# Development_board.net
KiCad netlist of a schematic drawn in EAGLE
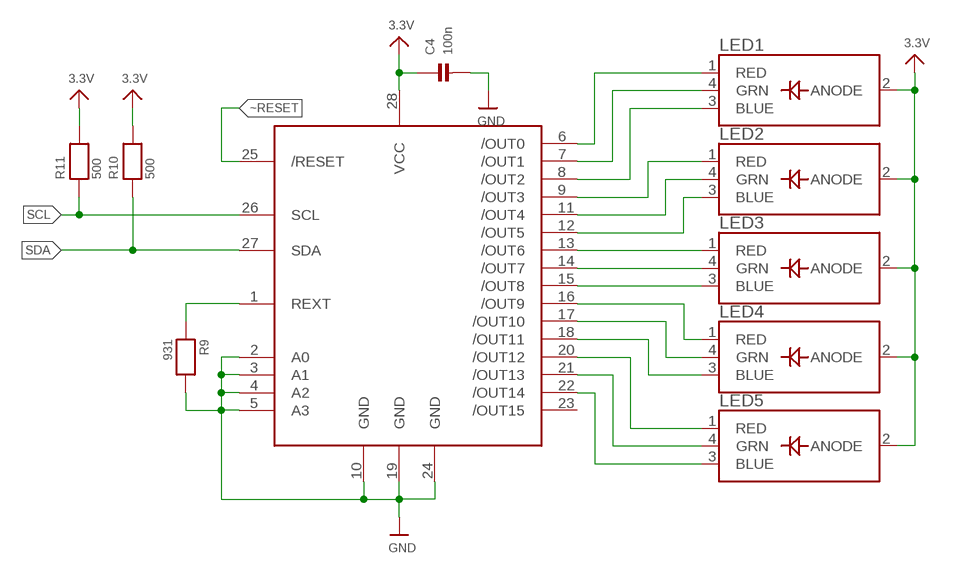
[diagram p0: schematic, sheet 1, part 1 of 3]
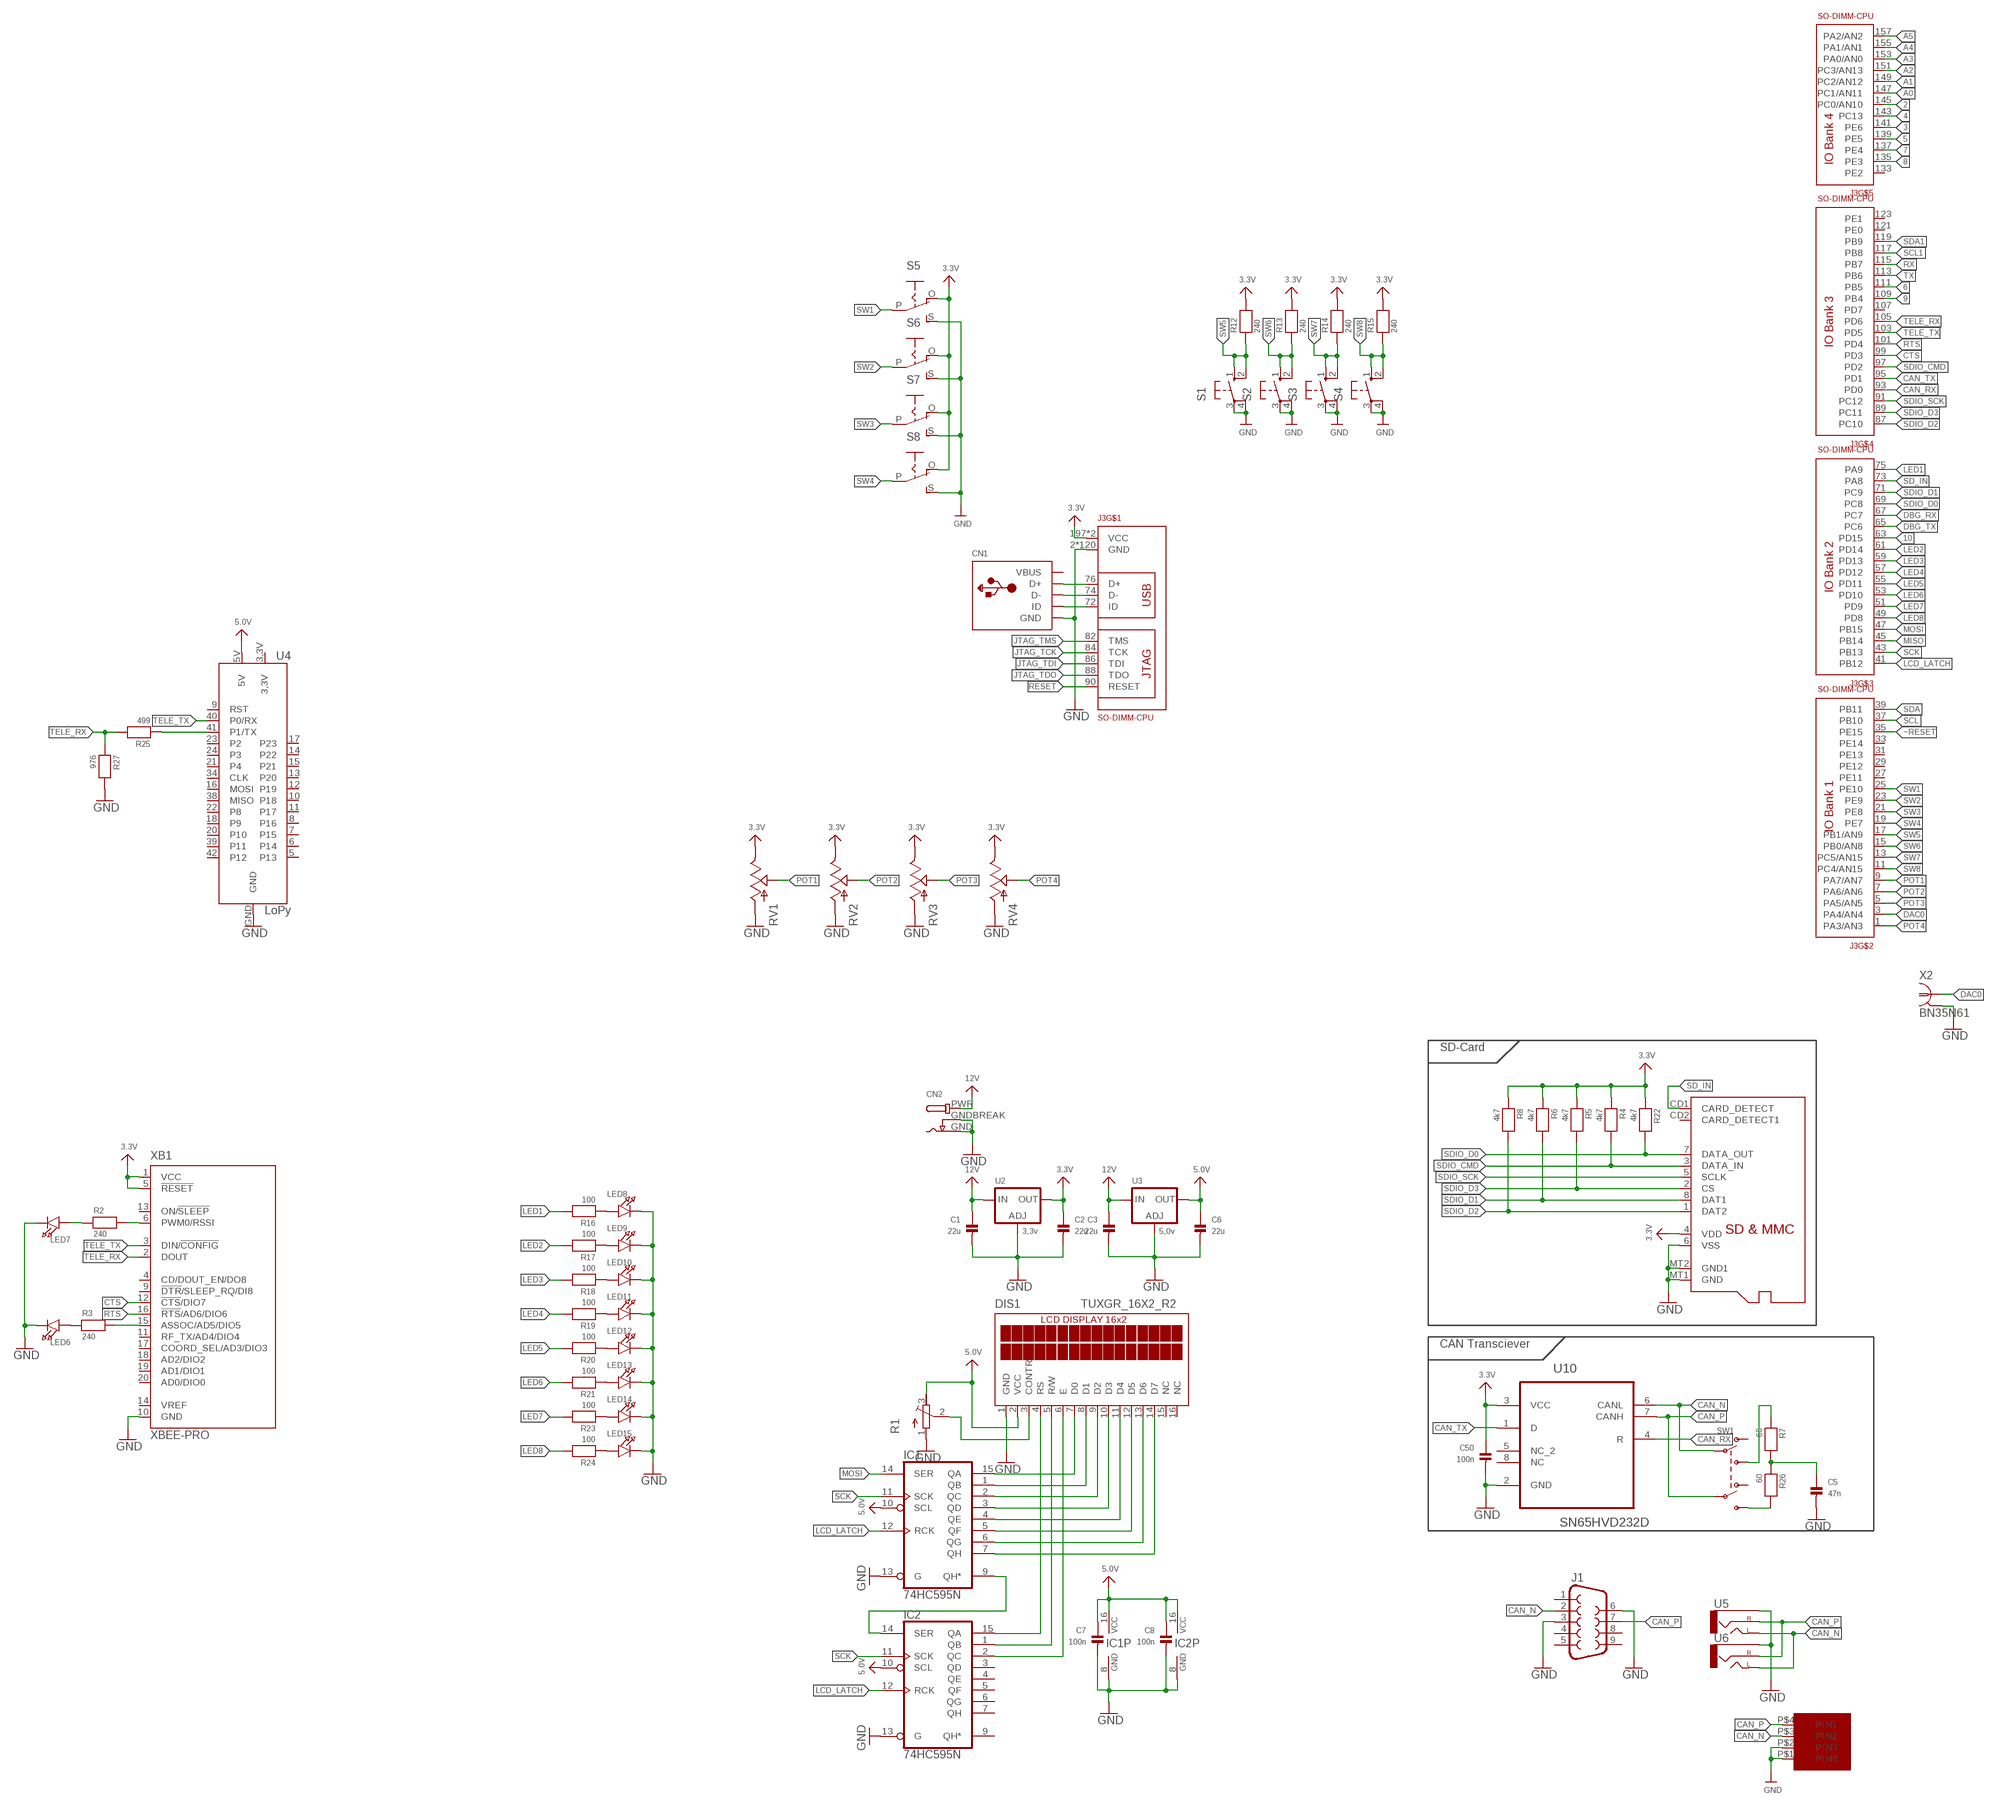
[diagram p1: schematic, sheet 1, part 2 of 3]
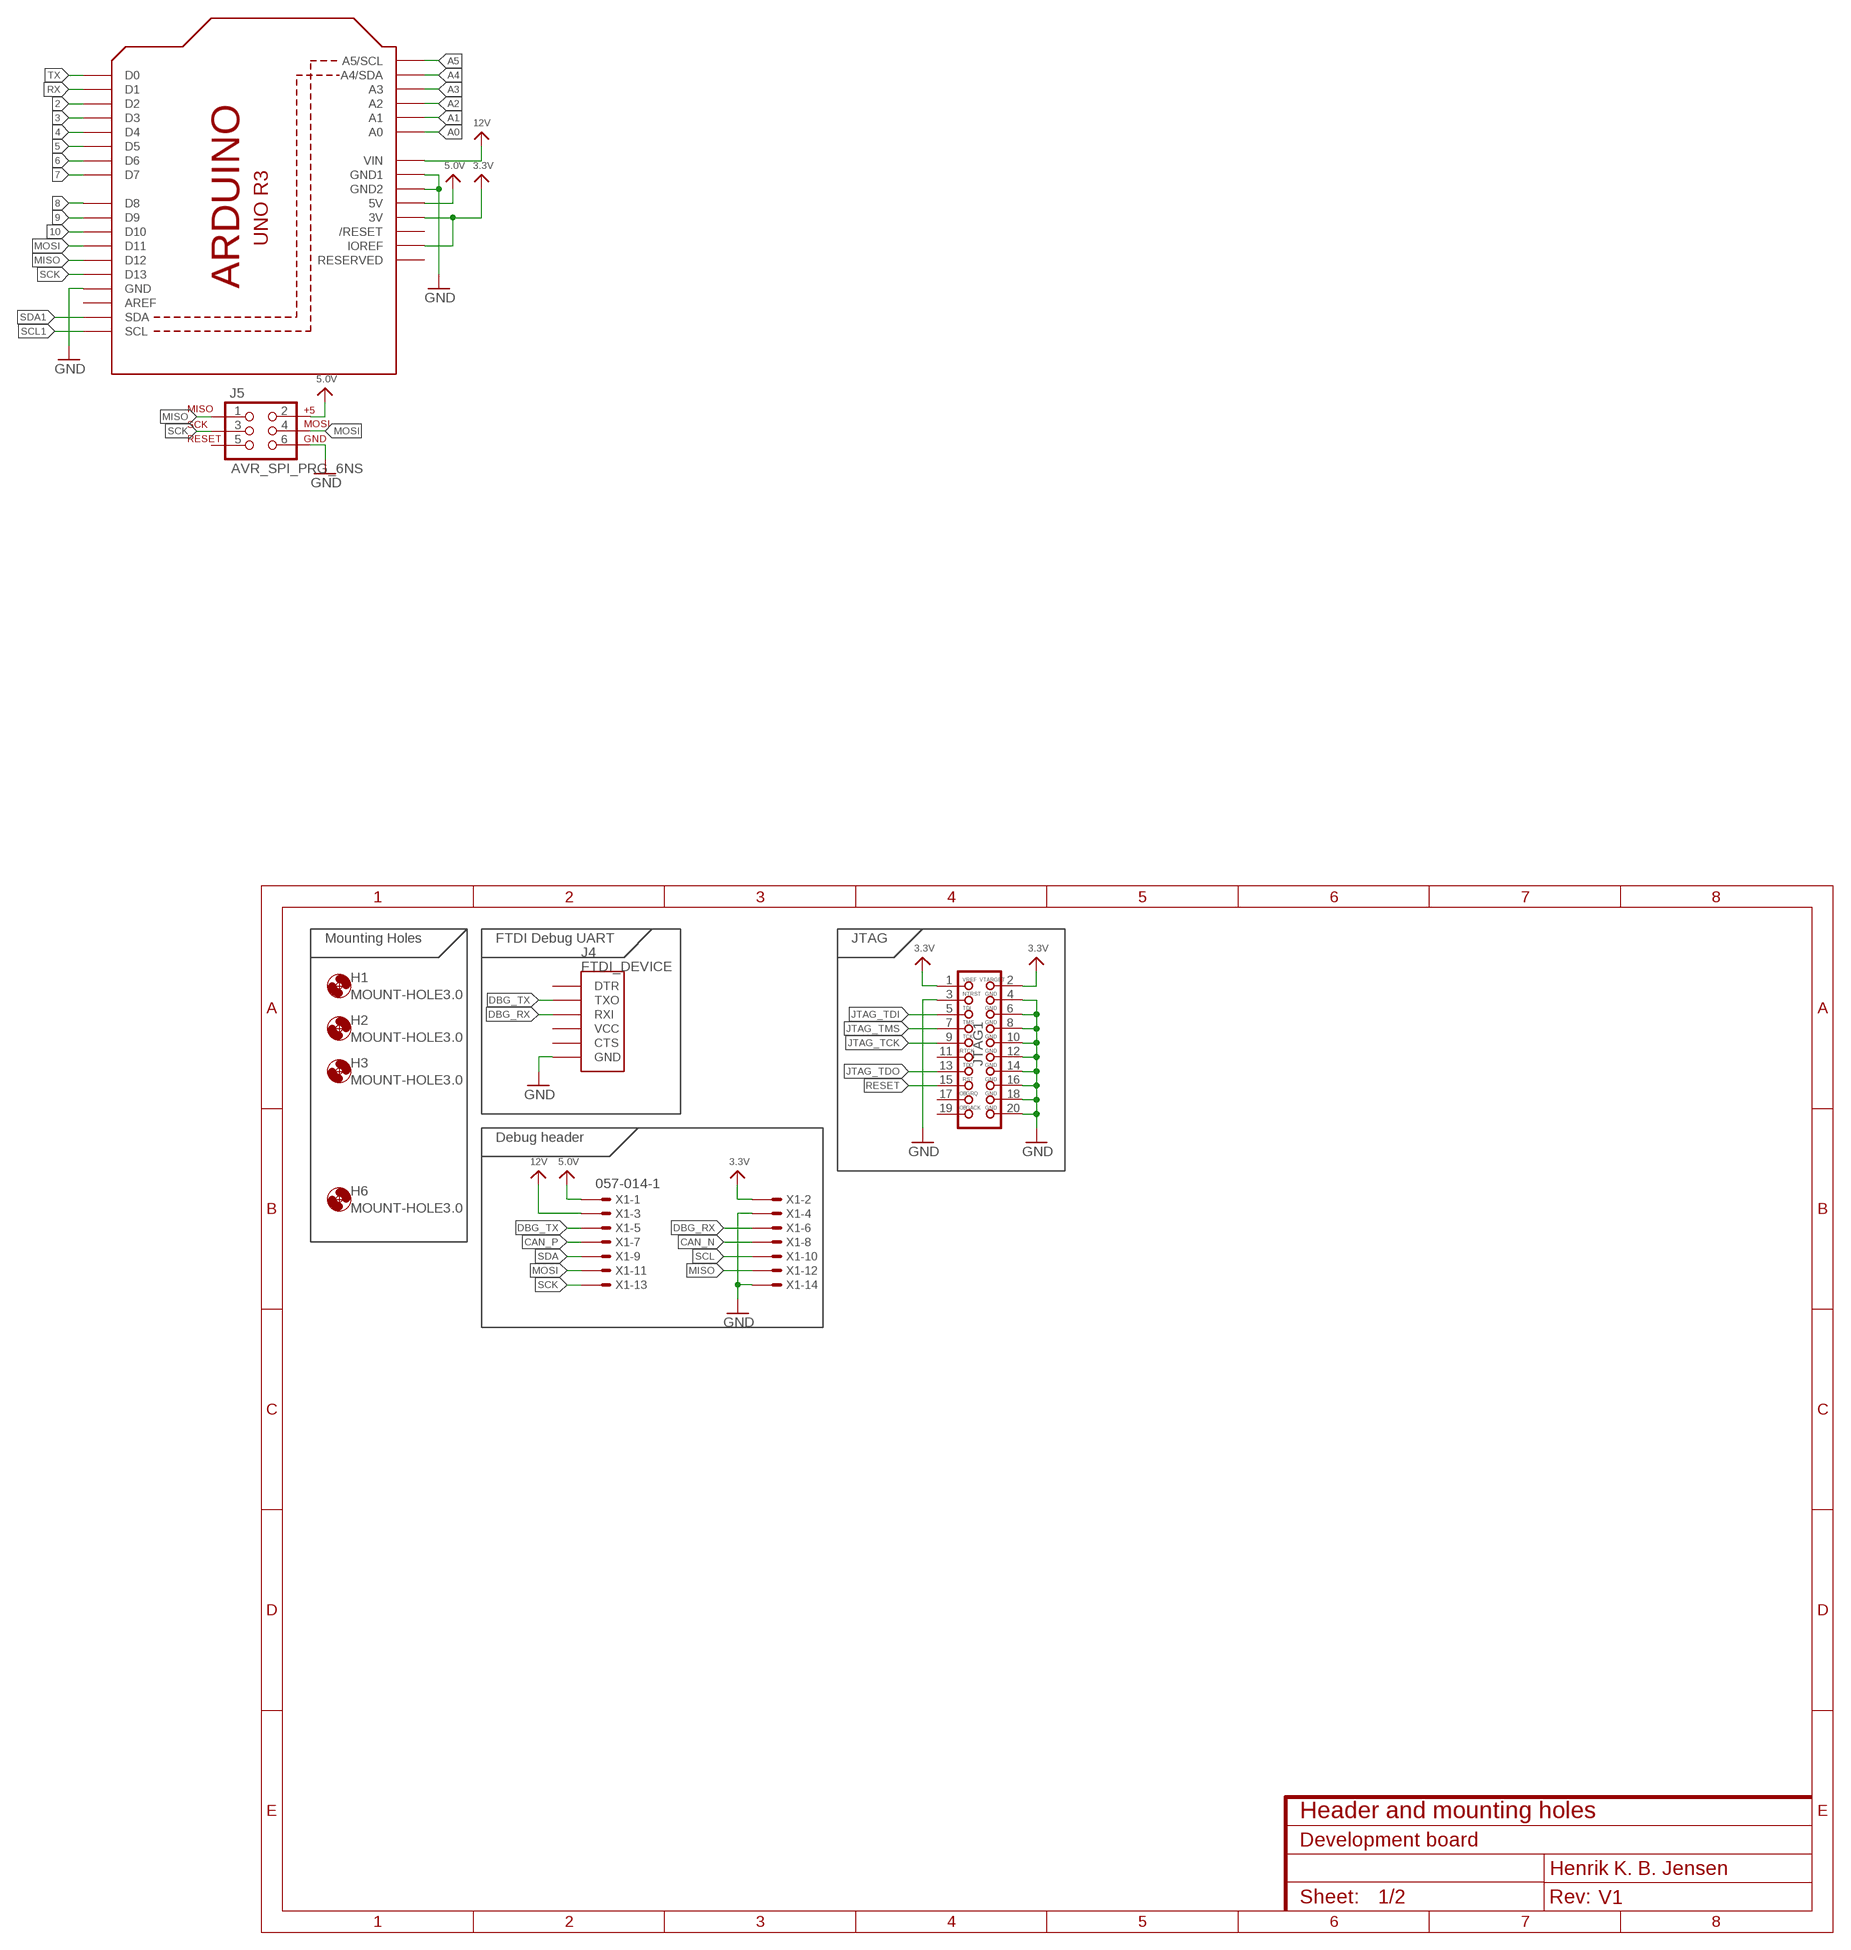
[diagram p2: schematic, sheet 1, part 3 of 3]
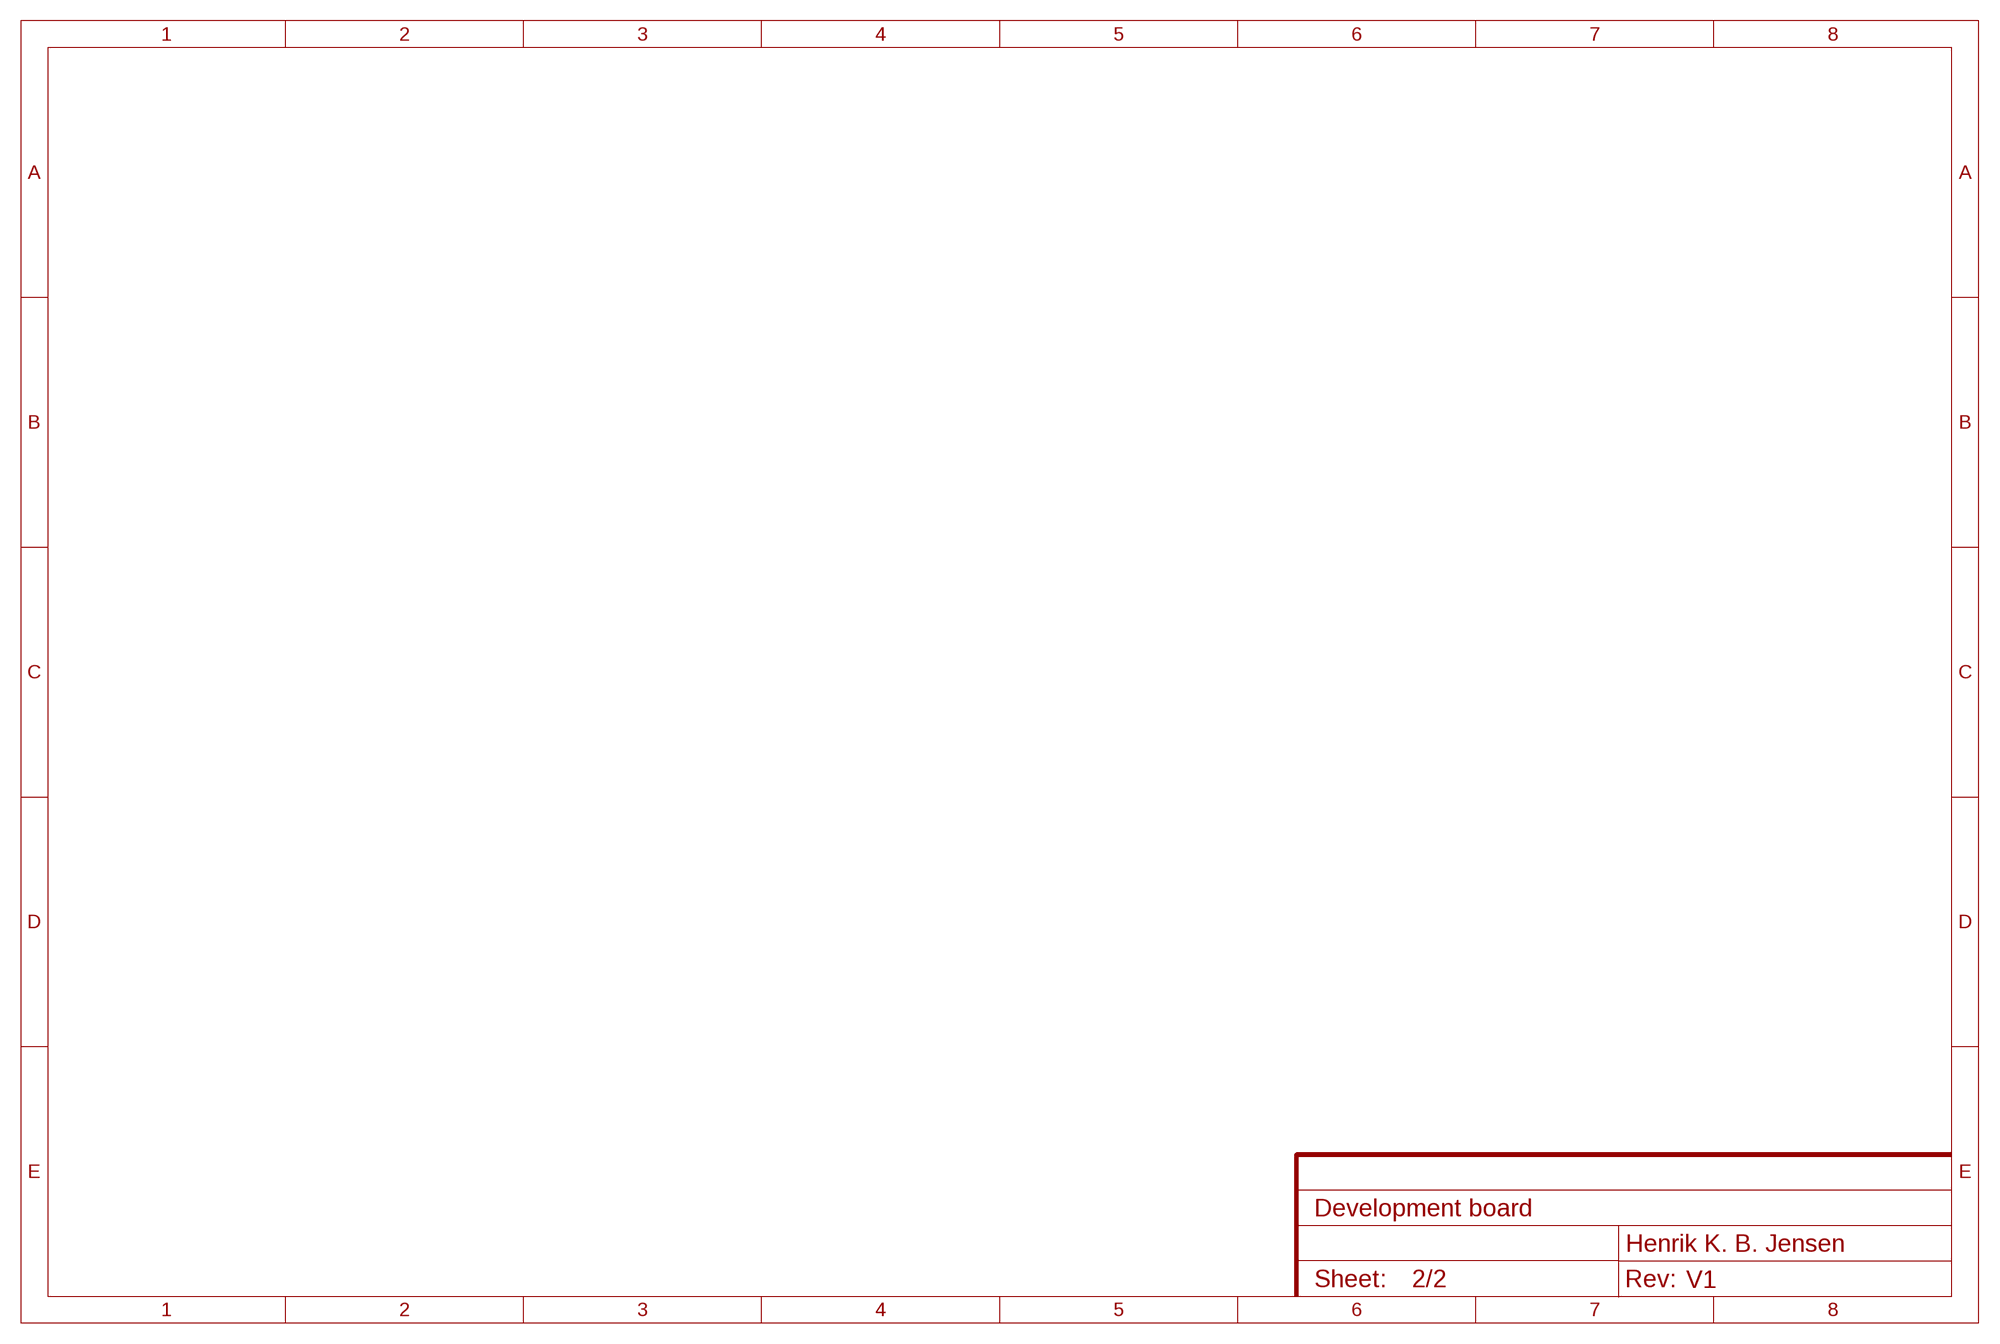
[diagram p3: schematic, sheet 2]

(export (version "E")
  (design (tool "Eeschema 10.0.6"))
  (components
    (comp (ref "C1")
      (value "22u")
      (footprint "eagle-import:_0805")
      (libsource (lib "eagle-import") (part "CAP_CERAMIC_0805"))
    )
    (comp (ref "C2")
      (value "22u")
      (footprint "eagle-import:_0805")
      (libsource (lib "eagle-import") (part "CAP_CERAMIC_0805"))
    )
    (comp (ref "C3")
      (value "22u")
      (footprint "eagle-import:_0805")
      (libsource (lib "eagle-import") (part "CAP_CERAMIC_0805"))
    )
    (comp (ref "C4")
      (value "100n")
      (footprint "eagle-import:_0603")
      (libsource (lib "eagle-import") (part "CAP_CERAMIC_0603"))
    )
    (comp (ref "C5")
      (value "47n")
      (footprint "eagle-import:_0603")
      (libsource (lib "eagle-import") (part "CAP_CERAMIC_0603"))
    )
    (comp (ref "C6")
      (value "22u")
      (footprint "eagle-import:_0805")
      (libsource (lib "eagle-import") (part "CAP_CERAMIC_0805"))
    )
    (comp (ref "C7")
      (value "100n")
      (footprint "eagle-import:_0603")
      (libsource (lib "eagle-import") (part "CAP_CERAMIC_0603"))
    )
    (comp (ref "C8")
      (value "100n")
      (footprint "eagle-import:_0603")
      (libsource (lib "eagle-import") (part "CAP_CERAMIC_0603"))
    )
    (comp (ref "C50")
      (value "100n")
      (footprint "eagle-import:_0603")
      (libsource (lib "eagle-import") (part "CAP_CERAMIC_0603"))
    )
    (comp (ref "CN1")
      (value "USBMINIBLARGE")
      (footprint "eagle-import:USB-MINIB_LARGER")
      (libsource (lib "eagle-import") (part "USBMINIBLARGE"))
    )
    (comp (ref "CN2")
      (value "DCBARRELPTH")
      (footprint "eagle-import:DCJACK_2MM_PTH")
      (libsource (lib "eagle-import") (part "DCBARRELPTH"))
    )
    (comp (ref "DIS1")
      (value "TUXGR_16X2_R2")
      (footprint "eagle-import:TUXGR_16X2_R2")
      (libsource (lib "eagle-import") (part "TUXGR_16X2_R2"))
    )
    (comp (ref "H1")
      (value "MOUNT-HOLE3.0")
      (footprint "eagle-import:3,0")
      (libsource (lib "eagle-import") (part "MOUNT-HOLE3.0"))
    )
    (comp (ref "H2")
      (value "MOUNT-HOLE3.0")
      (footprint "eagle-import:3,0")
      (libsource (lib "eagle-import") (part "MOUNT-HOLE3.0"))
    )
    (comp (ref "H3")
      (value "MOUNT-HOLE3.0")
      (footprint "eagle-import:3,0")
      (libsource (lib "eagle-import") (part "MOUNT-HOLE3.0"))
    )
    (comp (ref "H6")
      (value "MOUNT-HOLE3.0")
      (footprint "eagle-import:3,0")
      (libsource (lib "eagle-import") (part "MOUNT-HOLE3.0"))
    )
    (comp (ref "IC1")
      (value "74HC595N")
      (footprint "eagle-import:DIL16")
      (libsource (lib "eagle-import") (part "74595NHC"))
    )
    (comp (ref "IC2")
      (value "74HC595N")
      (footprint "eagle-import:DIL16")
      (libsource (lib "eagle-import") (part "74595NHC"))
    )
    (comp (ref "J1")
      (value "DB9FEMALE")
      (footprint "eagle-import:DB9")
      (libsource (lib "eagle-import") (part "DB9FEMALE"))
    )
    (comp (ref "J3")
      (value "SO-DIMM-CPU")
      (footprint "eagle-import:SODIMM-CONNECTOR-2.5V")
      (libsource (lib "eagle-import") (part "SO-DIMM-CPU"))
    )
    (comp (ref "J4")
      (value "FTDI_DEVICE")
      (footprint "eagle-import:FTDI_DEVICE_SIDE")
      (libsource (lib "eagle-import") (part "FTDI_DEVICE"))
    )
    (comp (ref "J5")
      (value "AVR_SPI_PRG_6NS")
      (footprint "eagle-import:2X3-NS")
      (libsource (lib "eagle-import") (part "AVR_SPI_PRG_6NS"))
    )
    (comp (ref "JTAG1")
      (value "JTAG-ARM")
      (footprint "eagle-import:JTAG-ARM")
      (libsource (lib "eagle-import") (part "JTAG-ARM"))
    )
    (comp (ref "LED1")
      (value "LED_RGB_PLCC4")
      (footprint "eagle-import:RGBLED_PLCC4")
      (libsource (lib "eagle-import") (part "LED_RGB_PLCC4"))
    )
    (comp (ref "LED2")
      (value "LED_RGB_PLCC4")
      (footprint "eagle-import:RGBLED_PLCC4")
      (libsource (lib "eagle-import") (part "LED_RGB_PLCC4"))
    )
    (comp (ref "LED3")
      (value "LED_RGB_PLCC4")
      (footprint "eagle-import:RGBLED_PLCC4")
      (libsource (lib "eagle-import") (part "LED_RGB_PLCC4"))
    )
    (comp (ref "LED4")
      (value "LED_RGB_PLCC4")
      (footprint "eagle-import:RGBLED_PLCC4")
      (libsource (lib "eagle-import") (part "LED_RGB_PLCC4"))
    )
    (comp (ref "LED5")
      (value "LED_RGB_PLCC4")
      (footprint "eagle-import:RGBLED_PLCC4")
      (libsource (lib "eagle-import") (part "LED_RGB_PLCC4"))
    )
    (comp (ref "LED6")
      (value "LED1206")
      (footprint "eagle-import:CHIPLED_1206")
      (libsource (lib "eagle-import") (part "LED1206"))
    )
    (comp (ref "LED7")
      (value "LED1206")
      (footprint "eagle-import:CHIPLED_1206")
      (libsource (lib "eagle-import") (part "LED1206"))
    )
    (comp (ref "LED8")
      (value "LED1206")
      (footprint "eagle-import:CHIPLED_1206")
      (libsource (lib "eagle-import") (part "LED1206"))
    )
    (comp (ref "LED9")
      (value "LED1206")
      (footprint "eagle-import:CHIPLED_1206")
      (libsource (lib "eagle-import") (part "LED1206"))
    )
    (comp (ref "LED10")
      (value "LED1206")
      (footprint "eagle-import:CHIPLED_1206")
      (libsource (lib "eagle-import") (part "LED1206"))
    )
    (comp (ref "LED11")
      (value "LED1206")
      (footprint "eagle-import:CHIPLED_1206")
      (libsource (lib "eagle-import") (part "LED1206"))
    )
    (comp (ref "LED12")
      (value "LED1206")
      (footprint "eagle-import:CHIPLED_1206")
      (libsource (lib "eagle-import") (part "LED1206"))
    )
    (comp (ref "LED13")
      (value "LED1206")
      (footprint "eagle-import:CHIPLED_1206")
      (libsource (lib "eagle-import") (part "LED1206"))
    )
    (comp (ref "LED14")
      (value "LED1206")
      (footprint "eagle-import:CHIPLED_1206")
      (libsource (lib "eagle-import") (part "LED1206"))
    )
    (comp (ref "LED15")
      (value "LED1206")
      (footprint "eagle-import:CHIPLED_1206")
      (libsource (lib "eagle-import") (part "LED1206"))
    )
    (comp (ref "R1")
      (value "R-TRIMM3296W")
      (footprint "eagle-import:RTRIM3296W")
      (libsource (lib "eagle-import") (part "R-TRIMM3296W"))
    )
    (comp (ref "R2")
      (value "240")
      (footprint "eagle-import:_0603")
      (libsource (lib "eagle-import") (part "RESISTOR_0603"))
    )
    (comp (ref "R3")
      (value "240")
      (footprint "eagle-import:_0603")
      (libsource (lib "eagle-import") (part "RESISTOR_0603"))
    )
    (comp (ref "R4")
      (value "4k7")
      (footprint "eagle-import:_0603")
      (libsource (lib "eagle-import") (part "RESISTOR_0603"))
    )
    (comp (ref "R5")
      (value "4k7")
      (footprint "eagle-import:_0603")
      (libsource (lib "eagle-import") (part "RESISTOR_0603"))
    )
    (comp (ref "R6")
      (value "4k7")
      (footprint "eagle-import:_0603")
      (libsource (lib "eagle-import") (part "RESISTOR_0603"))
    )
    (comp (ref "R7")
      (value "60")
      (footprint "eagle-import:_0603")
      (libsource (lib "eagle-import") (part "RESISTOR_0603"))
    )
    (comp (ref "R8")
      (value "4k7")
      (footprint "eagle-import:_0603")
      (libsource (lib "eagle-import") (part "RESISTOR_0603"))
    )
    (comp (ref "R9")
      (value "931")
      (footprint "eagle-import:_0603")
      (libsource (lib "eagle-import") (part "RESISTOR_0603"))
    )
    (comp (ref "R10")
      (value "500")
      (footprint "eagle-import:_0603")
      (libsource (lib "eagle-import") (part "RESISTOR_0603"))
    )
    (comp (ref "R11")
      (value "500")
      (footprint "eagle-import:_0603")
      (libsource (lib "eagle-import") (part "RESISTOR_0603"))
    )
    (comp (ref "R12")
      (value "240")
      (footprint "eagle-import:_0603")
      (libsource (lib "eagle-import") (part "RESISTOR_0603"))
    )
    (comp (ref "R13")
      (value "240")
      (footprint "eagle-import:_0603")
      (libsource (lib "eagle-import") (part "RESISTOR_0603"))
    )
    (comp (ref "R14")
      (value "240")
      (footprint "eagle-import:_0603")
      (libsource (lib "eagle-import") (part "RESISTOR_0603"))
    )
    (comp (ref "R15")
      (value "240")
      (footprint "eagle-import:_0603")
      (libsource (lib "eagle-import") (part "RESISTOR_0603"))
    )
    (comp (ref "R16")
      (value "100")
      (footprint "eagle-import:_0603")
      (libsource (lib "eagle-import") (part "RESISTOR_0603"))
    )
    (comp (ref "R17")
      (value "100")
      (footprint "eagle-import:_0603")
      (libsource (lib "eagle-import") (part "RESISTOR_0603"))
    )
    (comp (ref "R18")
      (value "100")
      (footprint "eagle-import:_0603")
      (libsource (lib "eagle-import") (part "RESISTOR_0603"))
    )
    (comp (ref "R19")
      (value "100")
      (footprint "eagle-import:_0603")
      (libsource (lib "eagle-import") (part "RESISTOR_0603"))
    )
    (comp (ref "R20")
      (value "100")
      (footprint "eagle-import:_0603")
      (libsource (lib "eagle-import") (part "RESISTOR_0603"))
    )
    (comp (ref "R21")
      (value "100")
      (footprint "eagle-import:_0603")
      (libsource (lib "eagle-import") (part "RESISTOR_0603"))
    )
    (comp (ref "R22")
      (value "4k7")
      (footprint "eagle-import:_0603")
      (libsource (lib "eagle-import") (part "RESISTOR_0603"))
    )
    (comp (ref "R23")
      (value "100")
      (footprint "eagle-import:_0603")
      (libsource (lib "eagle-import") (part "RESISTOR_0603"))
    )
    (comp (ref "R24")
      (value "100")
      (footprint "eagle-import:_0603")
      (libsource (lib "eagle-import") (part "RESISTOR_0603"))
    )
    (comp (ref "R25")
      (value "499")
      (footprint "eagle-import:_0603")
      (libsource (lib "eagle-import") (part "RESISTOR_0603"))
    )
    (comp (ref "R26")
      (value "60")
      (footprint "eagle-import:_0603")
      (libsource (lib "eagle-import") (part "RESISTOR_0603"))
    )
    (comp (ref "R27")
      (value "976")
      (footprint "eagle-import:_0603")
      (libsource (lib "eagle-import") (part "RESISTOR_0603"))
    )
    (comp (ref "RV1")
      (value "POT")
      (footprint "eagle-import:ALPS_POT")
      (libsource (lib "eagle-import") (part "POT"))
    )
    (comp (ref "RV2")
      (value "POT")
      (footprint "eagle-import:ALPS_POT")
      (libsource (lib "eagle-import") (part "POT"))
    )
    (comp (ref "RV3")
      (value "POT")
      (footprint "eagle-import:ALPS_POT")
      (libsource (lib "eagle-import") (part "POT"))
    )
    (comp (ref "RV4")
      (value "POT")
      (footprint "eagle-import:ALPS_POT")
      (libsource (lib "eagle-import") (part "POT"))
    )
    (comp (ref "S1")
      (value "10-XX")
      (footprint "eagle-import:B3F-10XX")
      (fields
        (field (name "MPN") "B3F-1000")
        (field (name "MPN_1") "B3F-1000")
        (field (name "OC_FARNELL") "176432")
        (field (name "OC_NEWARK") "36M3542")
      )
      (libsource (lib "eagle-import") (part "10-XX"))
    )
    (comp (ref "S2")
      (value "10-XX")
      (footprint "eagle-import:B3F-10XX")
      (fields
        (field (name "MPN") "B3F-1000")
        (field (name "MPN_1") "B3F-1000")
        (field (name "OC_FARNELL") "176432")
        (field (name "OC_NEWARK") "36M3542")
      )
      (libsource (lib "eagle-import") (part "10-XX"))
    )
    (comp (ref "S3")
      (value "10-XX")
      (footprint "eagle-import:B3F-10XX")
      (fields
        (field (name "MPN") "B3F-1000")
        (field (name "MPN_1") "B3F-1000")
        (field (name "OC_FARNELL") "176432")
        (field (name "OC_NEWARK") "36M3542")
      )
      (libsource (lib "eagle-import") (part "10-XX"))
    )
    (comp (ref "S4")
      (value "10-XX")
      (footprint "eagle-import:B3F-10XX")
      (fields
        (field (name "MPN") "B3F-1000")
        (field (name "MPN_1") "B3F-1000")
        (field (name "OC_FARNELL") "176432")
        (field (name "OC_NEWARK") "36M3542")
      )
      (libsource (lib "eagle-import") (part "10-XX"))
    )
    (comp (ref "S5")
      (value "EG1218S")
      (footprint "eagle-import:EG1218")
      (libsource (lib "eagle-import") (part "EG1218S"))
    )
    (comp (ref "S6")
      (value "EG1218S")
      (footprint "eagle-import:EG1218")
      (libsource (lib "eagle-import") (part "EG1218S"))
    )
    (comp (ref "S7")
      (value "EG1218S")
      (footprint "eagle-import:EG1218")
      (libsource (lib "eagle-import") (part "EG1218S"))
    )
    (comp (ref "S8")
      (value "EG1218S")
      (footprint "eagle-import:EG1218")
      (libsource (lib "eagle-import") (part "EG1218S"))
    )
    (comp (ref "SW1")
      (value "SWITCH_DPDT")
      (footprint "eagle-import:DPDT_SMT_JS202011SCQN")
      (libsource (lib "eagle-import") (part "SWITCH_DPDT"))
    )
    (comp (ref "U$2")
      (value "MICROSD")
      (footprint "eagle-import:MICROSD")
      (libsource (lib "eagle-import") (part "MICROSD"))
    )
    (comp (ref "U$21")
      (value "MICROFIT4")
      (footprint "eagle-import:43045-0400")
      (libsource (lib "eagle-import") (part "MICROFIT4"))
    )
    (comp (ref "U$30")
      (value "TLC59116")
      (footprint "eagle-import:TSSOP28")
      (libsource (lib "eagle-import") (part "TLC59116"))
    )
    (comp (ref "U1")
      (value "ARDUINOR3-DIMENSION")
      (footprint "eagle-import:ARDUINOR3")
      (libsource (lib "eagle-import") (part "ARDUINOR3-DIMENSION"))
    )
    (comp (ref "U2")
      (value "3,3v")
      (footprint "eagle-import:SOT223-R")
      (libsource (lib "eagle-import") (part "LM1117SOT223-REFLOW"))
    )
    (comp (ref "U3")
      (value "5,0v")
      (footprint "eagle-import:SOT223-R")
      (libsource (lib "eagle-import") (part "LM1117SOT223-REFLOW"))
    )
    (comp (ref "U4")
      (value "LoPy")
      (footprint "eagle-import:LOPY")
      (libsource (lib "eagle-import") (part "LOPY"))
    )
    (comp (ref "U5")
      (value "AUDIO-JACKPTH")
      (footprint "eagle-import:AUDIO-JACK")
      (libsource (lib "eagle-import") (part "AUDIO-JACKPTH"))
    )
    (comp (ref "U6")
      (value "AUDIO-JACKPTH")
      (footprint "eagle-import:AUDIO-JACK")
      (libsource (lib "eagle-import") (part "AUDIO-JACKPTH"))
    )
    (comp (ref "U10")
      (value "SN65HVD232D")
      (footprint "eagle-import:SOIC127P600X175-8N")
      (libsource (lib "eagle-import") (part "SN65HVD232D"))
    )
    (comp (ref "X1")
      (value "057-014-1")
      (footprint "eagle-import:057-014-1")
      (libsource (lib "eagle-import") (part "057-014-1"))
    )
    (comp (ref "X2")
      (value "BN35N61")
      (footprint "eagle-import:B35N61")
      (libsource (lib "eagle-import") (part "BN35N61"))
    )
    (comp (ref "XB1")
      (value "XBEE-PRO")
      (footprint "eagle-import:XBEE-PRO")
      (fields (field (name "MPN") "XBP24-AWI-001"))
      (libsource (lib "eagle-import") (part "XBEE-PRO"))
    )
  )
  (nets
    (net (code "1") (name "2") (class "Default")
      (node (ref "J3") (pin "145") (pinfunction "PC0/AN10_145") (pintype "bidirectional"))
      (node (ref "U1") (pin "D2") (pinfunction "D2_D2") (pintype "bidirectional"))
    )
    (net (code "2") (name "3") (class "Default")
      (node (ref "J3") (pin "141") (pinfunction "PE6_141") (pintype "bidirectional"))
      (node (ref "U1") (pin "D3") (pinfunction "D3_D3") (pintype "bidirectional"))
    )
    (net (code "3") (name "3.3V") (class "Default")
      (node (ref "C2") (pin "1") (pinfunction "P$1_1") (pintype "passive"))
      (node (ref "C4") (pin "1") (pinfunction "P$1_1") (pintype "passive"))
      (node (ref "C50") (pin "1") (pinfunction "P$1_1") (pintype "passive"))
      (node (ref "J3") (pin "197") (pinfunction "VCC_197") (pintype "bidirectional"))
      (node (ref "J3") (pin "199") (pinfunction "VCC_199") (pintype "bidirectional"))
      (node (ref "JTAG1") (pin "1") (pinfunction "1_1") (pintype "passive"))
      (node (ref "JTAG1") (pin "2") (pinfunction "2_2") (pintype "passive"))
      (node (ref "LED1") (pin "2") (pinfunction "ANODE_2") (pintype "power_in"))
      (node (ref "LED2") (pin "2") (pinfunction "ANODE_2") (pintype "power_in"))
      (node (ref "LED3") (pin "2") (pinfunction "ANODE_2") (pintype "power_in"))
      (node (ref "LED4") (pin "2") (pinfunction "ANODE_2") (pintype "power_in"))
      (node (ref "LED5") (pin "2") (pinfunction "ANODE_2") (pintype "power_in"))
      (node (ref "R10") (pin "2") (pinfunction "2_2") (pintype "passive"))
      (node (ref "R11") (pin "2") (pinfunction "2_2") (pintype "passive"))
      (node (ref "R12") (pin "2") (pinfunction "2_2") (pintype "passive"))
      (node (ref "R13") (pin "2") (pinfunction "2_2") (pintype "passive"))
      (node (ref "R14") (pin "2") (pinfunction "2_2") (pintype "passive"))
      (node (ref "R15") (pin "2") (pinfunction "2_2") (pintype "passive"))
      (node (ref "R22") (pin "1") (pinfunction "1_1") (pintype "passive"))
      (node (ref "R4") (pin "1") (pinfunction "1_1") (pintype "passive"))
      (node (ref "R5") (pin "1") (pinfunction "1_1") (pintype "passive"))
      (node (ref "R6") (pin "1") (pinfunction "1_1") (pintype "passive"))
      (node (ref "R8") (pin "1") (pinfunction "1_1") (pintype "passive"))
      (node (ref "RV1") (pin "P$1") (pinfunction "E_P$1") (pintype "passive"))
      (node (ref "RV2") (pin "P$1") (pinfunction "E_P$1") (pintype "passive"))
      (node (ref "RV3") (pin "P$1") (pinfunction "E_P$1") (pintype "passive"))
      (node (ref "RV4") (pin "P$1") (pinfunction "E_P$1") (pintype "passive"))
      (node (ref "S5") (pin "O") (pinfunction "O_O") (pintype "passive"))
      (node (ref "S6") (pin "O") (pinfunction "O_O") (pintype "passive"))
      (node (ref "S7") (pin "O") (pinfunction "O_O") (pintype "passive"))
      (node (ref "S8") (pin "O") (pinfunction "O_O") (pintype "passive"))
      (node (ref "U$2") (pin "4") (pinfunction "VDD_4") (pintype "power_in"))
      (node (ref "U$30") (pin "28") (pinfunction "VCC_28") (pintype "bidirectional"))
      (node (ref "U1") (pin "3V") (pinfunction "3V_3V") (pintype "power_in"))
      (node (ref "U1") (pin "IOREF") (pinfunction "IOREF_IOREF") (pintype "output"))
      (node (ref "U10") (pin "3") (pinfunction "VCC_3") (pintype "power_in"))
      (node (ref "U2") (pin "2") (pinfunction "OUT_2") (pintype "passive"))
      (node (ref "X1") (pin "2") (pinfunction "S_2") (pintype "passive"))
      (node (ref "XB1") (pin "1") (pinfunction "VCC_1") (pintype "power_in"))
      (node (ref "XB1") (pin "5") (pinfunction "~{RESET}_5") (pintype "input"))
    )
    (net (code "4") (name "4") (class "Default")
      (node (ref "J3") (pin "143") (pinfunction "PC13_143") (pintype "bidirectional"))
      (node (ref "U1") (pin "D4") (pinfunction "D4_D4") (pintype "bidirectional"))
    )
    (net (code "5") (name "5") (class "Default")
      (node (ref "J3") (pin "139") (pinfunction "PE5_139") (pintype "bidirectional"))
      (node (ref "U1") (pin "D5") (pinfunction "D5_D5") (pintype "bidirectional"))
    )
    (net (code "6") (name "5.0V") (class "Default")
      (node (ref "C6") (pin "1") (pinfunction "P$1_1") (pintype "passive"))
      (node (ref "C7") (pin "1") (pinfunction "P$1_1") (pintype "passive"))
      (node (ref "C8") (pin "1") (pinfunction "P$1_1") (pintype "passive"))
      (node (ref "DIS1") (pin "2") (pinfunction "VCC_2") (pintype "power_in"))
      (node (ref "IC1") (pin "10") (pinfunction "SCL_10") (pintype "input"))
      (node (ref "IC1") (pin "16") (pinfunction "VCC_16") (pintype "power_in"))
      (node (ref "IC2") (pin "10") (pinfunction "SCL_10") (pintype "input"))
      (node (ref "IC2") (pin "16") (pinfunction "VCC_16") (pintype "power_in"))
      (node (ref "J5") (pin "2") (pinfunction "2_2") (pintype "passive"))
      (node (ref "R1") (pin "3") (pinfunction "E_3") (pintype "passive"))
      (node (ref "U1") (pin "5V") (pinfunction "5V_5V") (pintype "power_in"))
      (node (ref "U3") (pin "2") (pinfunction "OUT_2") (pintype "passive"))
      (node (ref "U4") (pin "5V") (pinfunction "5V_5V") (pintype "bidirectional"))
      (node (ref "X1") (pin "1") (pinfunction "S_1") (pintype "passive"))
    )
    (net (code "7") (name "6") (class "Default")
      (node (ref "J3") (pin "111") (pinfunction "PB5_111") (pintype "bidirectional"))
      (node (ref "U1") (pin "D6") (pinfunction "D6_D6") (pintype "bidirectional"))
    )
    (net (code "8") (name "7") (class "Default")
      (node (ref "J3") (pin "137") (pinfunction "PE4_137") (pintype "bidirectional"))
      (node (ref "U1") (pin "D7") (pinfunction "D7_D7") (pintype "bidirectional"))
    )
    (net (code "9") (name "8") (class "Default")
      (node (ref "J3") (pin "135") (pinfunction "PE3_135") (pintype "bidirectional"))
      (node (ref "U1") (pin "D8") (pinfunction "D8_D8") (pintype "bidirectional"))
    )
    (net (code "10") (name "9") (class "Default")
      (node (ref "J3") (pin "109") (pinfunction "PB4_109") (pintype "bidirectional"))
      (node (ref "U1") (pin "D9") (pinfunction "D9_D9") (pintype "bidirectional"))
    )
    (net (code "11") (name "10") (class "Default")
      (node (ref "J3") (pin "63") (pinfunction "PD15_63") (pintype "bidirectional"))
      (node (ref "U1") (pin "D10") (pinfunction "D10_D10") (pintype "bidirectional"))
    )
    (net (code "12") (name "12V") (class "Default")
      (node (ref "C1") (pin "1") (pinfunction "P$1_1") (pintype "passive"))
      (node (ref "C3") (pin "1") (pinfunction "P$1_1") (pintype "passive"))
      (node (ref "CN2") (pin "PWR") (pinfunction "PWR_PWR") (pintype "power_in"))
      (node (ref "U1") (pin "VIN") (pinfunction "VIN_VIN") (pintype "power_in"))
      (node (ref "U2") (pin "3") (pinfunction "IN_3") (pintype "input"))
      (node (ref "U3") (pin "3") (pinfunction "IN_3") (pintype "input"))
      (node (ref "X1") (pin "3") (pinfunction "S_3") (pintype "passive"))
    )
    (net (code "13") (name "A0") (class "Default")
      (node (ref "J3") (pin "147") (pinfunction "PC1/AN11_147") (pintype "bidirectional"))
      (node (ref "U1") (pin "A0") (pinfunction "A0_A0") (pintype "bidirectional"))
    )
    (net (code "14") (name "A1") (class "Default")
      (node (ref "J3") (pin "149") (pinfunction "PC2/AN12_149") (pintype "bidirectional"))
      (node (ref "U1") (pin "A1") (pinfunction "A1_A1") (pintype "bidirectional"))
    )
    (net (code "15") (name "A2") (class "Default")
      (node (ref "J3") (pin "151") (pinfunction "PC3/AN13_151") (pintype "bidirectional"))
      (node (ref "U1") (pin "A2") (pinfunction "A2_A2") (pintype "bidirectional"))
    )
    (net (code "16") (name "A3") (class "Default")
      (node (ref "J3") (pin "153") (pinfunction "PA0/AN0_153") (pintype "bidirectional"))
      (node (ref "U1") (pin "A3") (pinfunction "A3_A3") (pintype "bidirectional"))
    )
    (net (code "17") (name "A4") (class "Default")
      (node (ref "J3") (pin "155") (pinfunction "PA1/AN1_155") (pintype "bidirectional"))
      (node (ref "U1") (pin "A4") (pinfunction "A4/SDA_A4") (pintype "bidirectional"))
    )
    (net (code "18") (name "A5") (class "Default")
      (node (ref "J3") (pin "157") (pinfunction "PA2/AN2_157") (pintype "bidirectional"))
      (node (ref "U1") (pin "A5") (pinfunction "A5/SCL_A5") (pintype "bidirectional"))
    )
    (net (code "19") (name "CAN_N") (class "Default")
      (node (ref "J1") (pin "2") (pinfunction "2_2") (pintype "passive"))
      (node (ref "SW1") (pin "P$2") (pinfunction "P1_P$2") (pintype "passive"))
      (node (ref "U$21") (pin "P$3") (pinfunction "PIN2_P$3") (pintype "bidirectional"))
      (node (ref "U10") (pin "6") (pinfunction "CANL_6") (pintype "output"))
      (node (ref "U5") (pin "TIP") (pinfunction "LEFT_TIP") (pintype "bidirectional"))
      (node (ref "U6") (pin "TIP") (pinfunction "LEFT_TIP") (pintype "bidirectional"))
      (node (ref "X1") (pin "8") (pinfunction "S_8") (pintype "passive"))
    )
    (net (code "20") (name "CAN_P") (class "Default")
      (node (ref "J1") (pin "7") (pinfunction "7_7") (pintype "passive"))
      (node (ref "SW1") (pin "P$5") (pinfunction "P2_P$5") (pintype "passive"))
      (node (ref "U$21") (pin "P$4") (pinfunction "PIN1_P$4") (pintype "bidirectional"))
      (node (ref "U10") (pin "7") (pinfunction "CANH_7") (pintype "output"))
      (node (ref "U5") (pin "RING") (pinfunction "RIGHT_RING") (pintype "bidirectional"))
      (node (ref "U6") (pin "RING") (pinfunction "RIGHT_RING") (pintype "bidirectional"))
      (node (ref "X1") (pin "7") (pinfunction "S_7") (pintype "passive"))
    )
    (net (code "21") (name "CAN_RX") (class "Default")
      (node (ref "J3") (pin "93") (pinfunction "PD0_93") (pintype "bidirectional"))
      (node (ref "U10") (pin "4") (pinfunction "R_4") (pintype "output"))
    )
    (net (code "22") (name "CAN_TX") (class "Default")
      (node (ref "J3") (pin "95") (pinfunction "PD1_95") (pintype "bidirectional"))
      (node (ref "U10") (pin "1") (pinfunction "D_1") (pintype "input"))
    )
    (net (code "23") (name "CTS") (class "Default")
      (node (ref "J3") (pin "99") (pinfunction "PD3_99") (pintype "bidirectional"))
      (node (ref "XB1") (pin "12") (pinfunction "~{CTS}/DIO7_12") (pintype "bidirectional"))
    )
    (net (code "24") (name "DAC0") (class "Default")
      (node (ref "J3") (pin "3") (pinfunction "PA4/AN4_3") (pintype "bidirectional"))
      (node (ref "X2") (pin "1") (pinfunction "1_1") (pintype "passive"))
    )
    (net (code "25") (name "DBG_RX") (class "Default")
      (node (ref "J3") (pin "67") (pinfunction "PC7_67") (pintype "bidirectional"))
      (node (ref "J4") (pin "P$3") (pinfunction "RXI_P$3") (pintype "bidirectional"))
      (node (ref "X1") (pin "6") (pinfunction "S_6") (pintype "passive"))
    )
    (net (code "26") (name "DBG_TX") (class "Default")
      (node (ref "J3") (pin "65") (pinfunction "PC6_65") (pintype "bidirectional"))
      (node (ref "J4") (pin "P$2") (pinfunction "TXO_P$2") (pintype "bidirectional"))
      (node (ref "X1") (pin "5") (pinfunction "S_5") (pintype "passive"))
    )
    (net (code "27") (name "GND") (class "Default")
      (node (ref "C1") (pin "2") (pinfunction "P$2_2") (pintype "passive"))
      (node (ref "C2") (pin "2") (pinfunction "P$2_2") (pintype "passive"))
      (node (ref "C3") (pin "2") (pinfunction "P$2_2") (pintype "passive"))
      (node (ref "C4") (pin "2") (pinfunction "P$2_2") (pintype "passive"))
      (node (ref "C5") (pin "2") (pinfunction "P$2_2") (pintype "passive"))
      (node (ref "C50") (pin "2") (pinfunction "P$2_2") (pintype "passive"))
      (node (ref "C6") (pin "2") (pinfunction "P$2_2") (pintype "passive"))
      (node (ref "C7") (pin "2") (pinfunction "P$2_2") (pintype "passive"))
      (node (ref "C8") (pin "2") (pinfunction "P$2_2") (pintype "passive"))
      (node (ref "CN1") (pin "GND") (pinfunction "GND_GND") (pintype "power_in"))
      (node (ref "CN2") (pin "GND") (pinfunction "GND_GND") (pintype "power_in"))
      (node (ref "CN2") (pin "GNDBREAK") (pinfunction "GNDBREAK_GNDBREAK") (pintype "power_in"))
      (node (ref "DIS1") (pin "1") (pinfunction "GND_1") (pintype "power_in"))
      (node (ref "IC1") (pin "13") (pinfunction "G_13") (pintype "input"))
      (node (ref "IC1") (pin "8") (pinfunction "GND_8") (pintype "power_in"))
      (node (ref "IC2") (pin "13") (pinfunction "G_13") (pintype "input"))
      (node (ref "IC2") (pin "8") (pinfunction "GND_8") (pintype "power_in"))
      (node (ref "J1") (pin "3") (pinfunction "3_3") (pintype "passive"))
      (node (ref "J1") (pin "6") (pinfunction "6_6") (pintype "passive"))
      (node (ref "J3") (pin "10") (pinfunction "GND_10") (pintype "bidirectional"))
      (node (ref "J3") (pin "100") (pinfunction "GND_100") (pintype "bidirectional"))
      (node (ref "J3") (pin "102") (pinfunction "GND_102") (pintype "bidirectional"))
      (node (ref "J3") (pin "104") (pinfunction "GND_104") (pintype "bidirectional"))
      (node (ref "J3") (pin "106") (pinfunction "GND_106") (pintype "bidirectional"))
      (node (ref "J3") (pin "108") (pinfunction "GND_108") (pintype "bidirectional"))
      (node (ref "J3") (pin "110") (pinfunction "GND_110") (pintype "bidirectional"))
      (node (ref "J3") (pin "112") (pinfunction "GND_112") (pintype "bidirectional"))
      (node (ref "J3") (pin "114") (pinfunction "GND_114") (pintype "bidirectional"))
      (node (ref "J3") (pin "116") (pinfunction "GND_116") (pintype "bidirectional"))
      (node (ref "J3") (pin "118") (pinfunction "GND_118") (pintype "bidirectional"))
      (node (ref "J3") (pin "12") (pinfunction "GND_12") (pintype "bidirectional"))
      (node (ref "J3") (pin "120") (pinfunction "GND_120") (pintype "bidirectional"))
      (node (ref "J3") (pin "122") (pinfunction "GND_122") (pintype "bidirectional"))
      (node (ref "J3") (pin "124") (pinfunction "GND_124") (pintype "bidirectional"))
      (node (ref "J3") (pin "125") (pinfunction "GND_125") (pintype "bidirectional"))
      (node (ref "J3") (pin "126") (pinfunction "GND_126") (pintype "bidirectional"))
      (node (ref "J3") (pin "127") (pinfunction "GND_127") (pintype "bidirectional"))
      (node (ref "J3") (pin "128") (pinfunction "GND_128") (pintype "bidirectional"))
      (node (ref "J3") (pin "129") (pinfunction "GND_129") (pintype "bidirectional"))
      (node (ref "J3") (pin "130") (pinfunction "GND_130") (pintype "bidirectional"))
      (node (ref "J3") (pin "131") (pinfunction "GND_131") (pintype "bidirectional"))
      (node (ref "J3") (pin "132") (pinfunction "GND_132") (pintype "bidirectional"))
      (node (ref "J3") (pin "134") (pinfunction "GND_134") (pintype "bidirectional"))
      (node (ref "J3") (pin "136") (pinfunction "GND_136") (pintype "bidirectional"))
      (node (ref "J3") (pin "138") (pinfunction "GND_138") (pintype "bidirectional"))
      (node (ref "J3") (pin "14") (pinfunction "GND_14") (pintype "bidirectional"))
      (node (ref "J3") (pin "140") (pinfunction "GND_140") (pintype "bidirectional"))
      (node (ref "J3") (pin "142") (pinfunction "GND_142") (pintype "bidirectional"))
      (node (ref "J3") (pin "144") (pinfunction "GND_144") (pintype "bidirectional"))
      (node (ref "J3") (pin "146") (pinfunction "GND_146") (pintype "bidirectional"))
      (node (ref "J3") (pin "148") (pinfunction "GND_148") (pintype "bidirectional"))
      (node (ref "J3") (pin "150") (pinfunction "GND_150") (pintype "bidirectional"))
      (node (ref "J3") (pin "152") (pinfunction "GND_152") (pintype "bidirectional"))
      (node (ref "J3") (pin "154") (pinfunction "GND_154") (pintype "bidirectional"))
      (node (ref "J3") (pin "156") (pinfunction "GND_156") (pintype "bidirectional"))
      (node (ref "J3") (pin "158") (pinfunction "GND_158") (pintype "bidirectional"))
      (node (ref "J3") (pin "159") (pinfunction "GND_159") (pintype "bidirectional"))
      (node (ref "J3") (pin "16") (pinfunction "GND_16") (pintype "bidirectional"))
      (node (ref "J3") (pin "160") (pinfunction "GND_160") (pintype "bidirectional"))
      (node (ref "J3") (pin "161") (pinfunction "GND_161") (pintype "bidirectional"))
      (node (ref "J3") (pin "162") (pinfunction "GND_162") (pintype "bidirectional"))
      (node (ref "J3") (pin "163") (pinfunction "GND_163") (pintype "bidirectional"))
      (node (ref "J3") (pin "164") (pinfunction "GND_164") (pintype "bidirectional"))
      (node (ref "J3") (pin "165") (pinfunction "GND_165") (pintype "bidirectional"))
      (node (ref "J3") (pin "166") (pinfunction "GND_166") (pintype "bidirectional"))
      (node (ref "J3") (pin "167") (pinfunction "GND_167") (pintype "bidirectional"))
      (node (ref "J3") (pin "168") (pinfunction "GND_168") (pintype "bidirectional"))
      (node (ref "J3") (pin "169") (pinfunction "GND_169") (pintype "bidirectional"))
      (node (ref "J3") (pin "170") (pinfunction "GND_170") (pintype "bidirectional"))
      (node (ref "J3") (pin "171") (pinfunction "GND_171") (pintype "bidirectional"))
      (node (ref "J3") (pin "172") (pinfunction "GND_172") (pintype "bidirectional"))
      (node (ref "J3") (pin "173") (pinfunction "GND_173") (pintype "bidirectional"))
      (node (ref "J3") (pin "174") (pinfunction "GND_174") (pintype "bidirectional"))
      (node (ref "J3") (pin "175") (pinfunction "GND_175") (pintype "bidirectional"))
      (node (ref "J3") (pin "176") (pinfunction "GND_176") (pintype "bidirectional"))
      (node (ref "J3") (pin "177") (pinfunction "GND_177") (pintype "bidirectional"))
      (node (ref "J3") (pin "178") (pinfunction "GND_178") (pintype "bidirectional"))
      (node (ref "J3") (pin "179") (pinfunction "GND_179") (pintype "bidirectional"))
      (node (ref "J3") (pin "18") (pinfunction "GND_18") (pintype "bidirectional"))
      (node (ref "J3") (pin "180") (pinfunction "GND_180") (pintype "bidirectional"))
      (node (ref "J3") (pin "181") (pinfunction "GND_181") (pintype "bidirectional"))
      (node (ref "J3") (pin "182") (pinfunction "GND_182") (pintype "bidirectional"))
      (node (ref "J3") (pin "183") (pinfunction "GND_183") (pintype "bidirectional"))
      (node (ref "J3") (pin "184") (pinfunction "GND_184") (pintype "bidirectional"))
      (node (ref "J3") (pin "185") (pinfunction "GND_185") (pintype "bidirectional"))
      (node (ref "J3") (pin "186") (pinfunction "GND_186") (pintype "bidirectional"))
      (node (ref "J3") (pin "187") (pinfunction "GND_187") (pintype "bidirectional"))
      (node (ref "J3") (pin "188") (pinfunction "GND_188") (pintype "bidirectional"))
      (node (ref "J3") (pin "189") (pinfunction "GND_189") (pintype "bidirectional"))
      (node (ref "J3") (pin "190") (pinfunction "GND_190") (pintype "bidirectional"))
      (node (ref "J3") (pin "191") (pinfunction "GND_191") (pintype "bidirectional"))
      (node (ref "J3") (pin "192") (pinfunction "GND_192") (pintype "bidirectional"))
      (node (ref "J3") (pin "193") (pinfunction "GND_193") (pintype "bidirectional"))
      (node (ref "J3") (pin "194") (pinfunction "GND_194") (pintype "bidirectional"))
      (node (ref "J3") (pin "195") (pinfunction "GND_195") (pintype "bidirectional"))
      (node (ref "J3") (pin "196") (pinfunction "GND_196") (pintype "bidirectional"))
      (node (ref "J3") (pin "198") (pinfunction "GND_198") (pintype "bidirectional"))
      (node (ref "J3") (pin "2") (pinfunction "GND_2") (pintype "bidirectional"))
      (node (ref "J3") (pin "20") (pinfunction "GND_20") (pintype "bidirectional"))
      (node (ref "J3") (pin "200") (pinfunction "GND_200") (pintype "bidirectional"))
      (node (ref "J3") (pin "22") (pinfunction "GND_22") (pintype "bidirectional"))
      (node (ref "J3") (pin "24") (pinfunction "GND_24") (pintype "bidirectional"))
      (node (ref "J3") (pin "26") (pinfunction "GND_26") (pintype "bidirectional"))
      (node (ref "J3") (pin "28") (pinfunction "GND_28") (pintype "bidirectional"))
      (node (ref "J3") (pin "30") (pinfunction "GND_30") (pintype "bidirectional"))
      (node (ref "J3") (pin "32") (pinfunction "GND_32") (pintype "bidirectional"))
      (node (ref "J3") (pin "34") (pinfunction "GND_34") (pintype "bidirectional"))
      (node (ref "J3") (pin "36") (pinfunction "GND_36") (pintype "bidirectional"))
      (node (ref "J3") (pin "38") (pinfunction "GND_38") (pintype "bidirectional"))
      (node (ref "J3") (pin "4") (pinfunction "GND_4") (pintype "bidirectional"))
      (node (ref "J3") (pin "40") (pinfunction "GND_40") (pintype "bidirectional"))
      (node (ref "J3") (pin "42") (pinfunction "GND_42") (pintype "bidirectional"))
      (node (ref "J3") (pin "44") (pinfunction "GND_44") (pintype "bidirectional"))
      (node (ref "J3") (pin "46") (pinfunction "GND_46") (pintype "bidirectional"))
      (node (ref "J3") (pin "48") (pinfunction "GND_48") (pintype "bidirectional"))
      (node (ref "J3") (pin "50") (pinfunction "GND_50") (pintype "bidirectional"))
      (node (ref "J3") (pin "52") (pinfunction "GND_52") (pintype "bidirectional"))
      (node (ref "J3") (pin "54") (pinfunction "GND_54") (pintype "bidirectional"))
      (node (ref "J3") (pin "56") (pinfunction "GND_56") (pintype "bidirectional"))
      (node (ref "J3") (pin "58") (pinfunction "GND_58") (pintype "bidirectional"))
      (node (ref "J3") (pin "6") (pinfunction "GND_6") (pintype "bidirectional"))
      (node (ref "J3") (pin "60") (pinfunction "GND_60") (pintype "bidirectional"))
      (node (ref "J3") (pin "62") (pinfunction "GND_62") (pintype "bidirectional"))
      (node (ref "J3") (pin "64") (pinfunction "GND_64") (pintype "bidirectional"))
      (node (ref "J3") (pin "66") (pinfunction "GND_66") (pintype "bidirectional"))
      (node (ref "J3") (pin "68") (pinfunction "GND_68") (pintype "bidirectional"))
      (node (ref "J3") (pin "70") (pinfunction "GND_70") (pintype "bidirectional"))
      (node (ref "J3") (pin "77") (pinfunction "GND_77") (pintype "bidirectional"))
      (node (ref "J3") (pin "78") (pinfunction "GND_78") (pintype "bidirectional"))
      (node (ref "J3") (pin "79") (pinfunction "GND_79") (pintype "bidirectional"))
      (node (ref "J3") (pin "8") (pinfunction "GND_8") (pintype "bidirectional"))
      (node (ref "J3") (pin "80") (pinfunction "GND_80") (pintype "bidirectional"))
      (node (ref "J3") (pin "81") (pinfunction "GND_81") (pintype "bidirectional"))
      (node (ref "J3") (pin "83") (pinfunction "GND_83") (pintype "bidirectional"))
      (node (ref "J3") (pin "85") (pinfunction "GND_85") (pintype "bidirectional"))
      (node (ref "J3") (pin "92") (pinfunction "GND_92") (pintype "bidirectional"))
      (node (ref "J3") (pin "94") (pinfunction "GND_94") (pintype "bidirectional"))
      (node (ref "J3") (pin "96") (pinfunction "GND_96") (pintype "bidirectional"))
      (node (ref "J3") (pin "98") (pinfunction "GND_98") (pintype "bidirectional"))
      (node (ref "J4") (pin "P$6") (pinfunction "GND_P$6") (pintype "bidirectional"))
      (node (ref "J5") (pin "6") (pinfunction "6_6") (pintype "passive"))
      (node (ref "JTAG1") (pin "10") (pinfunction "10_10") (pintype "passive"))
      (node (ref "JTAG1") (pin "12") (pinfunction "12_12") (pintype "passive"))
      (node (ref "JTAG1") (pin "14") (pinfunction "14_14") (pintype "passive"))
      (node (ref "JTAG1") (pin "16") (pinfunction "16_16") (pintype "passive"))
      (node (ref "JTAG1") (pin "18") (pinfunction "18_18") (pintype "passive"))
      (node (ref "JTAG1") (pin "20") (pinfunction "20_20") (pintype "passive"))
      (node (ref "JTAG1") (pin "3") (pinfunction "3_3") (pintype "passive"))
      (node (ref "JTAG1") (pin "4") (pinfunction "4_4") (pintype "passive"))
      (node (ref "JTAG1") (pin "6") (pinfunction "6_6") (pintype "passive"))
      (node (ref "JTAG1") (pin "8") (pinfunction "8_8") (pintype "passive"))
      (node (ref "LED10") (pin "C") (pinfunction "C_C") (pintype "passive"))
      (node (ref "LED11") (pin "C") (pinfunction "C_C") (pintype "passive"))
      (node (ref "LED12") (pin "C") (pinfunction "C_C") (pintype "passive"))
      (node (ref "LED13") (pin "C") (pinfunction "C_C") (pintype "passive"))
      (node (ref "LED14") (pin "C") (pinfunction "C_C") (pintype "passive"))
      (node (ref "LED15") (pin "C") (pinfunction "C_C") (pintype "passive"))
      (node (ref "LED6") (pin "C") (pinfunction "C_C") (pintype "passive"))
      (node (ref "LED7") (pin "C") (pinfunction "C_C") (pintype "passive"))
      (node (ref "LED8") (pin "C") (pinfunction "C_C") (pintype "passive"))
      (node (ref "LED9") (pin "C") (pinfunction "C_C") (pintype "passive"))
      (node (ref "R1") (pin "1") (pinfunction "A_1") (pintype "passive"))
      (node (ref "R27") (pin "2") (pinfunction "2_2") (pintype "passive"))
      (node (ref "R9") (pin "2") (pinfunction "2_2") (pintype "passive"))
      (node (ref "RV1") (pin "P$3") (pinfunction "A_P$3") (pintype "passive"))
      (node (ref "RV2") (pin "P$3") (pinfunction "A_P$3") (pintype "passive"))
      (node (ref "RV3") (pin "P$3") (pinfunction "A_P$3") (pintype "passive"))
      (node (ref "RV4") (pin "P$3") (pinfunction "A_P$3") (pintype "passive"))
      (node (ref "S1") (pin "3") (pinfunction "P_3") (pintype "passive"))
      (node (ref "S1") (pin "4") (pinfunction "P1_4") (pintype "passive"))
      (node (ref "S2") (pin "3") (pinfunction "P_3") (pintype "passive"))
      (node (ref "S2") (pin "4") (pinfunction "P1_4") (pintype "passive"))
      (node (ref "S3") (pin "3") (pinfunction "P_3") (pintype "passive"))
      (node (ref "S3") (pin "4") (pinfunction "P1_4") (pintype "passive"))
      (node (ref "S4") (pin "3") (pinfunction "P_3") (pintype "passive"))
      (node (ref "S4") (pin "4") (pinfunction "P1_4") (pintype "passive"))
      (node (ref "S5") (pin "S") (pinfunction "S_S") (pintype "passive"))
      (node (ref "S6") (pin "S") (pinfunction "S_S") (pintype "passive"))
      (node (ref "S7") (pin "S") (pinfunction "S_S") (pintype "passive"))
      (node (ref "S8") (pin "S") (pinfunction "S_S") (pintype "passive"))
      (node (ref "U$2") (pin "6") (pinfunction "VSS_6") (pintype "power_in"))
      (node (ref "U$2") (pin "MT1") (pinfunction "GND_MT1") (pintype "power_in"))
      (node (ref "U$2") (pin "MT2") (pinfunction "GND1_MT2") (pintype "power_in"))
      (node (ref "U$21") (pin "P$1") (pinfunction "PIN4_P$1") (pintype "bidirectional"))
      (node (ref "U$21") (pin "P$2") (pinfunction "PIN3_P$2") (pintype "bidirectional"))
      (node (ref "U$30") (pin "10") (pinfunction "GND_10") (pintype "bidirectional"))
      (node (ref "U$30") (pin "19") (pinfunction "GND_19") (pintype "bidirectional"))
      (node (ref "U$30") (pin "2") (pinfunction "A0_2") (pintype "bidirectional"))
      (node (ref "U$30") (pin "24") (pinfunction "GND_24") (pintype "bidirectional"))
      (node (ref "U$30") (pin "3") (pinfunction "A1_3") (pintype "bidirectional"))
      (node (ref "U$30") (pin "4") (pinfunction "A2_4") (pintype "bidirectional"))
      (node (ref "U$30") (pin "5") (pinfunction "A3_5") (pintype "bidirectional"))
      (node (ref "U1") (pin "GND") (pinfunction "GND_GND") (pintype "power_in"))
      (node (ref "U1") (pin "GND1") (pinfunction "GND1_GND1") (pintype "power_in"))
      (node (ref "U1") (pin "GND2") (pinfunction "GND2_GND2") (pintype "power_in"))
      (node (ref "U10") (pin "2") (pinfunction "GND_2") (pintype "passive"))
      (node (ref "U2") (pin "1") (pinfunction "ADJ_1") (pintype "input"))
      (node (ref "U3") (pin "1") (pinfunction "ADJ_1") (pintype "input"))
      (node (ref "U4") (pin "GND") (pinfunction "GND_GND") (pintype "bidirectional"))
      (node (ref "U5") (pin "SLEEVE") (pinfunction "SLEEVE_SLEEVE") (pintype "bidirectional"))
      (node (ref "U6") (pin "SLEEVE") (pinfunction "SLEEVE_SLEEVE") (pintype "bidirectional"))
      (node (ref "X1") (pin "14") (pinfunction "S_14") (pintype "passive"))
      (node (ref "X1") (pin "4") (pinfunction "S_4") (pintype "passive"))
      (node (ref "X2") (pin "2") (pinfunction "GND_2") (pintype "power_in"))
      (node (ref "XB1") (pin "10") (pinfunction "GND_10") (pintype "power_in"))
    )
    (net (code "28") (name "JTAG_TCK") (class "Default")
      (node (ref "J3") (pin "84") (pinfunction "TCK_84") (pintype "bidirectional"))
      (node (ref "JTAG1") (pin "9") (pinfunction "9_9") (pintype "passive"))
    )
    (net (code "29") (name "JTAG_TDI") (class "Default")
      (node (ref "J3") (pin "86") (pinfunction "TDI_86") (pintype "bidirectional"))
      (node (ref "JTAG1") (pin "5") (pinfunction "5_5") (pintype "passive"))
    )
    (net (code "30") (name "JTAG_TDO") (class "Default")
      (node (ref "J3") (pin "88") (pinfunction "TDO_88") (pintype "bidirectional"))
      (node (ref "JTAG1") (pin "13") (pinfunction "13_13") (pintype "passive"))
    )
    (net (code "31") (name "JTAG_TMS") (class "Default")
      (node (ref "J3") (pin "82") (pinfunction "TMS_82") (pintype "bidirectional"))
      (node (ref "JTAG1") (pin "7") (pinfunction "7_7") (pintype "passive"))
    )
    (net (code "32") (name "LCD_LATCH") (class "Default")
      (node (ref "IC1") (pin "12") (pinfunction "RCK_12") (pintype "input"))
      (node (ref "IC2") (pin "12") (pinfunction "RCK_12") (pintype "input"))
      (node (ref "J3") (pin "41") (pinfunction "PB12_41") (pintype "bidirectional"))
    )
    (net (code "33") (name "LED1") (class "Default")
      (node (ref "J3") (pin "75") (pinfunction "PA9_75") (pintype "bidirectional"))
      (node (ref "R16") (pin "2") (pinfunction "2_2") (pintype "passive"))
    )
    (net (code "34") (name "LED2") (class "Default")
      (node (ref "J3") (pin "61") (pinfunction "PD14_61") (pintype "bidirectional"))
      (node (ref "R17") (pin "2") (pinfunction "2_2") (pintype "passive"))
    )
    (net (code "35") (name "LED3") (class "Default")
      (node (ref "J3") (pin "59") (pinfunction "PD13_59") (pintype "bidirectional"))
      (node (ref "R18") (pin "2") (pinfunction "2_2") (pintype "passive"))
    )
    (net (code "36") (name "LED4") (class "Default")
      (node (ref "J3") (pin "57") (pinfunction "PD12_57") (pintype "bidirectional"))
      (node (ref "R19") (pin "2") (pinfunction "2_2") (pintype "passive"))
    )
    (net (code "37") (name "LED5") (class "Default")
      (node (ref "J3") (pin "55") (pinfunction "PD11_55") (pintype "bidirectional"))
      (node (ref "R20") (pin "2") (pinfunction "2_2") (pintype "passive"))
    )
    (net (code "38") (name "LED6") (class "Default")
      (node (ref "J3") (pin "53") (pinfunction "PD10_53") (pintype "bidirectional"))
      (node (ref "R21") (pin "2") (pinfunction "2_2") (pintype "passive"))
    )
    (net (code "39") (name "LED7") (class "Default")
      (node (ref "J3") (pin "51") (pinfunction "PD9_51") (pintype "bidirectional"))
      (node (ref "R23") (pin "2") (pinfunction "2_2") (pintype "passive"))
    )
    (net (code "40") (name "LED8") (class "Default")
      (node (ref "J3") (pin "49") (pinfunction "PD8_49") (pintype "bidirectional"))
      (node (ref "R24") (pin "2") (pinfunction "2_2") (pintype "passive"))
    )
    (net (code "41") (name "MISO") (class "Default")
      (node (ref "J3") (pin "45") (pinfunction "PB14_45") (pintype "bidirectional"))
      (node (ref "J5") (pin "1") (pinfunction "1_1") (pintype "passive"))
      (node (ref "U1") (pin "D12") (pinfunction "D12_D12") (pintype "bidirectional"))
      (node (ref "X1") (pin "12") (pinfunction "S_12") (pintype "passive"))
    )
    (net (code "42") (name "MOSI") (class "Default")
      (node (ref "IC1") (pin "14") (pinfunction "SER_14") (pintype "input"))
      (node (ref "J3") (pin "47") (pinfunction "PB15_47") (pintype "bidirectional"))
      (node (ref "J5") (pin "4") (pinfunction "4_4") (pintype "passive"))
      (node (ref "U1") (pin "D11") (pinfunction "D11_D11") (pintype "bidirectional"))
      (node (ref "X1") (pin "11") (pinfunction "S_11") (pintype "passive"))
    )
    (net (code "43") (name "Net-(C5-P$1)") (class "Default")
      (node (ref "C5") (pin "1") (pinfunction "P$1_1") (pintype "passive"))
      (node (ref "R26") (pin "1") (pinfunction "1_1") (pintype "passive"))
      (node (ref "R7") (pin "2") (pinfunction "2_2") (pintype "passive"))
    )
    (net (code "44") (name "Net-(DIS1-CONTR)") (class "Default")
      (node (ref "DIS1") (pin "3") (pinfunction "CONTR_3") (pintype "input"))
      (node (ref "R1") (pin "2") (pinfunction "S_2") (pintype "passive"))
    )
    (net (code "45") (name "Net-(DIS1-D0)") (class "Default")
      (node (ref "DIS1") (pin "7") (pinfunction "D0_7") (pintype "input"))
      (node (ref "IC1") (pin "15") (pinfunction "QA_15") (pintype "tri_state"))
    )
    (net (code "46") (name "Net-(DIS1-D1)") (class "Default")
      (node (ref "DIS1") (pin "8") (pinfunction "D1_8") (pintype "input"))
      (node (ref "IC1") (pin "1") (pinfunction "QB_1") (pintype "tri_state"))
    )
    (net (code "47") (name "Net-(DIS1-D2)") (class "Default")
      (node (ref "DIS1") (pin "9") (pinfunction "D2_9") (pintype "input"))
      (node (ref "IC1") (pin "2") (pinfunction "QC_2") (pintype "tri_state"))
    )
    (net (code "48") (name "Net-(DIS1-D3)") (class "Default")
      (node (ref "DIS1") (pin "10") (pinfunction "D3_10") (pintype "input"))
      (node (ref "IC1") (pin "3") (pinfunction "QD_3") (pintype "tri_state"))
    )
    (net (code "49") (name "Net-(DIS1-D4)") (class "Default")
      (node (ref "DIS1") (pin "11") (pinfunction "D4_11") (pintype "input"))
      (node (ref "IC1") (pin "4") (pinfunction "QE_4") (pintype "tri_state"))
    )
    (net (code "50") (name "Net-(DIS1-D5)") (class "Default")
      (node (ref "DIS1") (pin "12") (pinfunction "D5_12") (pintype "input"))
      (node (ref "IC1") (pin "5") (pinfunction "QF_5") (pintype "tri_state"))
    )
    (net (code "51") (name "Net-(DIS1-D6)") (class "Default")
      (node (ref "DIS1") (pin "13") (pinfunction "D6_13") (pintype "input"))
      (node (ref "IC1") (pin "6") (pinfunction "QG_6") (pintype "tri_state"))
    )
    (net (code "52") (name "Net-(DIS1-D7)") (class "Default")
      (node (ref "DIS1") (pin "14") (pinfunction "D7_14") (pintype "input"))
      (node (ref "IC1") (pin "7") (pinfunction "QH_7") (pintype "tri_state"))
    )
    (net (code "53") (name "Net-(DIS1-E)") (class "Default")
      (node (ref "DIS1") (pin "6") (pinfunction "E_6") (pintype "input"))
      (node (ref "IC2") (pin "2") (pinfunction "QC_2") (pintype "tri_state"))
    )
    (net (code "54") (name "Net-(DIS1-RS)") (class "Default")
      (node (ref "DIS1") (pin "4") (pinfunction "RS_4") (pintype "input"))
      (node (ref "IC2") (pin "15") (pinfunction "QA_15") (pintype "tri_state"))
    )
    (net (code "55") (name "Net-(DIS1-R{slash}W)") (class "Default")
      (node (ref "DIS1") (pin "5") (pinfunction "R/W_5") (pintype "input"))
      (node (ref "IC2") (pin "1") (pinfunction "QB_1") (pintype "tri_state"))
    )
    (net (code "56") (name "Net-(IC1A-QH*)") (class "Default")
      (node (ref "IC1") (pin "9") (pinfunction "QH*_9") (pintype "tri_state"))
      (node (ref "IC2") (pin "14") (pinfunction "SER_14") (pintype "input"))
    )
    (net (code "57") (name "Net-(J3A-D+)") (class "Default")
      (node (ref "CN1") (pin "D+") (pinfunction "D+_D+") (pintype "bidirectional"))
      (node (ref "J3") (pin "76") (pinfunction "D+_76") (pintype "bidirectional"))
    )
    (net (code "58") (name "Net-(J3A-D-)") (class "Default")
      (node (ref "CN1") (pin "D-") (pinfunction "D-_D-") (pintype "bidirectional"))
      (node (ref "J3") (pin "74") (pinfunction "D-_74") (pintype "bidirectional"))
    )
    (net (code "59") (name "Net-(J3A-ID)") (class "Default")
      (node (ref "CN1") (pin "ID") (pinfunction "ID_ID") (pintype "bidirectional"))
      (node (ref "J3") (pin "72") (pinfunction "ID_72") (pintype "bidirectional"))
    )
    (net (code "60") (name "Net-(LED1-BLUE)") (class "Default")
      (node (ref "LED1") (pin "3") (pinfunction "BLUE_3") (pintype "bidirectional"))
      (node (ref "U$30") (pin "8") (pinfunction "/OUT2_8") (pintype "bidirectional"))
    )
    (net (code "61") (name "Net-(LED1-GRN)") (class "Default")
      (node (ref "LED1") (pin "4") (pinfunction "GRN_4") (pintype "bidirectional"))
      (node (ref "U$30") (pin "7") (pinfunction "/OUT1_7") (pintype "bidirectional"))
    )
    (net (code "62") (name "Net-(LED1-RED)") (class "Default")
      (node (ref "LED1") (pin "1") (pinfunction "RED_1") (pintype "bidirectional"))
      (node (ref "U$30") (pin "6") (pinfunction "/OUT0_6") (pintype "bidirectional"))
    )
    (net (code "63") (name "Net-(LED2-BLUE)") (class "Default")
      (node (ref "LED2") (pin "3") (pinfunction "BLUE_3") (pintype "bidirectional"))
      (node (ref "U$30") (pin "12") (pinfunction "/OUT5_12") (pintype "bidirectional"))
    )
    (net (code "64") (name "Net-(LED2-GRN)") (class "Default")
      (node (ref "LED2") (pin "4") (pinfunction "GRN_4") (pintype "bidirectional"))
      (node (ref "U$30") (pin "11") (pinfunction "/OUT4_11") (pintype "bidirectional"))
    )
    (net (code "65") (name "Net-(LED2-RED)") (class "Default")
      (node (ref "LED2") (pin "1") (pinfunction "RED_1") (pintype "bidirectional"))
      (node (ref "U$30") (pin "9") (pinfunction "/OUT3_9") (pintype "bidirectional"))
    )
    (net (code "66") (name "Net-(LED3-BLUE)") (class "Default")
      (node (ref "LED3") (pin "3") (pinfunction "BLUE_3") (pintype "bidirectional"))
      (node (ref "U$30") (pin "15") (pinfunction "/OUT8_15") (pintype "bidirectional"))
    )
    (net (code "67") (name "Net-(LED3-GRN)") (class "Default")
      (node (ref "LED3") (pin "4") (pinfunction "GRN_4") (pintype "bidirectional"))
      (node (ref "U$30") (pin "14") (pinfunction "/OUT7_14") (pintype "bidirectional"))
    )
    (net (code "68") (name "Net-(LED3-RED)") (class "Default")
      (node (ref "LED3") (pin "1") (pinfunction "RED_1") (pintype "bidirectional"))
      (node (ref "U$30") (pin "13") (pinfunction "/OUT6_13") (pintype "bidirectional"))
    )
    (net (code "69") (name "Net-(LED4-BLUE)") (class "Default")
      (node (ref "LED4") (pin "3") (pinfunction "BLUE_3") (pintype "bidirectional"))
      (node (ref "U$30") (pin "18") (pinfunction "/OUT11_18") (pintype "bidirectional"))
    )
    (net (code "70") (name "Net-(LED4-GRN)") (class "Default")
      (node (ref "LED4") (pin "4") (pinfunction "GRN_4") (pintype "bidirectional"))
      (node (ref "U$30") (pin "17") (pinfunction "/OUT10_17") (pintype "bidirectional"))
    )
    (net (code "71") (name "Net-(LED4-RED)") (class "Default")
      (node (ref "LED4") (pin "1") (pinfunction "RED_1") (pintype "bidirectional"))
      (node (ref "U$30") (pin "16") (pinfunction "/OUT9_16") (pintype "bidirectional"))
    )
    (net (code "72") (name "Net-(LED5-BLUE)") (class "Default")
      (node (ref "LED5") (pin "3") (pinfunction "BLUE_3") (pintype "bidirectional"))
      (node (ref "U$30") (pin "22") (pinfunction "/OUT14_22") (pintype "bidirectional"))
    )
    (net (code "73") (name "Net-(LED5-GRN)") (class "Default")
      (node (ref "LED5") (pin "4") (pinfunction "GRN_4") (pintype "bidirectional"))
      (node (ref "U$30") (pin "21") (pinfunction "/OUT13_21") (pintype "bidirectional"))
    )
    (net (code "74") (name "Net-(LED5-RED)") (class "Default")
      (node (ref "LED5") (pin "1") (pinfunction "RED_1") (pintype "bidirectional"))
      (node (ref "U$30") (pin "20") (pinfunction "/OUT12_20") (pintype "bidirectional"))
    )
    (net (code "75") (name "Net-(LED6-PadA)") (class "Default")
      (node (ref "LED6") (pin "A") (pinfunction "A_A") (pintype "passive"))
      (node (ref "R3") (pin "1") (pinfunction "1_1") (pintype "passive"))
    )
    (net (code "76") (name "Net-(LED7-PadA)") (class "Default")
      (node (ref "LED7") (pin "A") (pinfunction "A_A") (pintype "passive"))
      (node (ref "R2") (pin "1") (pinfunction "1_1") (pintype "passive"))
    )
    (net (code "77") (name "Net-(LED8-PadA)") (class "Default")
      (node (ref "LED8") (pin "A") (pinfunction "A_A") (pintype "passive"))
      (node (ref "R16") (pin "1") (pinfunction "1_1") (pintype "passive"))
    )
    (net (code "78") (name "Net-(LED9-PadA)") (class "Default")
      (node (ref "LED9") (pin "A") (pinfunction "A_A") (pintype "passive"))
      (node (ref "R17") (pin "1") (pinfunction "1_1") (pintype "passive"))
    )
    (net (code "79") (name "Net-(LED10-PadA)") (class "Default")
      (node (ref "LED10") (pin "A") (pinfunction "A_A") (pintype "passive"))
      (node (ref "R18") (pin "1") (pinfunction "1_1") (pintype "passive"))
    )
    (net (code "80") (name "Net-(LED11-PadA)") (class "Default")
      (node (ref "LED11") (pin "A") (pinfunction "A_A") (pintype "passive"))
      (node (ref "R19") (pin "1") (pinfunction "1_1") (pintype "passive"))
    )
    (net (code "81") (name "Net-(LED12-PadA)") (class "Default")
      (node (ref "LED12") (pin "A") (pinfunction "A_A") (pintype "passive"))
      (node (ref "R20") (pin "1") (pinfunction "1_1") (pintype "passive"))
    )
    (net (code "82") (name "Net-(LED13-PadA)") (class "Default")
      (node (ref "LED13") (pin "A") (pinfunction "A_A") (pintype "passive"))
      (node (ref "R21") (pin "1") (pinfunction "1_1") (pintype "passive"))
    )
    (net (code "83") (name "Net-(LED14-PadA)") (class "Default")
      (node (ref "LED14") (pin "A") (pinfunction "A_A") (pintype "passive"))
      (node (ref "R23") (pin "1") (pinfunction "1_1") (pintype "passive"))
    )
    (net (code "84") (name "Net-(LED15-PadA)") (class "Default")
      (node (ref "LED15") (pin "A") (pinfunction "A_A") (pintype "passive"))
      (node (ref "R24") (pin "1") (pinfunction "1_1") (pintype "passive"))
    )
    (net (code "85") (name "Net-(SW1-S1)") (class "Default")
      (node (ref "R7") (pin "1") (pinfunction "1_1") (pintype "passive"))
      (node (ref "SW1") (pin "P$3") (pinfunction "S1_P$3") (pintype "passive"))
    )
    (net (code "86") (name "Net-(SW1-S2)") (class "Default")
      (node (ref "R26") (pin "2") (pinfunction "2_2") (pintype "passive"))
      (node (ref "SW1") (pin "P$4") (pinfunction "S2_P$4") (pintype "passive"))
    )
    (net (code "87") (name "Net-(U$30-REXT)") (class "Default")
      (node (ref "R9") (pin "1") (pinfunction "1_1") (pintype "passive"))
      (node (ref "U$30") (pin "1") (pinfunction "REXT_1") (pintype "bidirectional"))
    )
    (net (code "88") (name "Net-(U4-P1{slash}TX)") (class "Default")
      (node (ref "R25") (pin "1") (pinfunction "1_1") (pintype "passive"))
      (node (ref "U4") (pin "41") (pinfunction "P1/TX_41") (pintype "bidirectional"))
    )
    (net (code "89") (name "Net-(XB1-ASSOC{slash}AD5{slash}DIO5)") (class "Default")
      (node (ref "R3") (pin "2") (pinfunction "2_2") (pintype "passive"))
      (node (ref "XB1") (pin "15") (pinfunction "ASSOC/AD5/DIO5_15") (pintype "bidirectional"))
    )
    (net (code "90") (name "Net-(XB1-PWM0{slash}RSSI)") (class "Default")
      (node (ref "R2") (pin "2") (pinfunction "2_2") (pintype "passive"))
      (node (ref "XB1") (pin "6") (pinfunction "PWM0/RSSI_6") (pintype "output"))
    )
    (net (code "91") (name "POT1") (class "Default")
      (node (ref "J3") (pin "9") (pinfunction "PA7/AN7_9") (pintype "bidirectional"))
      (node (ref "RV1") (pin "P$2") (pinfunction "S_P$2") (pintype "passive"))
    )
    (net (code "92") (name "POT2") (class "Default")
      (node (ref "J3") (pin "7") (pinfunction "PA6/AN6_7") (pintype "bidirectional"))
      (node (ref "RV2") (pin "P$2") (pinfunction "S_P$2") (pintype "passive"))
    )
    (net (code "93") (name "POT3") (class "Default")
      (node (ref "J3") (pin "5") (pinfunction "PA5/AN5_5") (pintype "bidirectional"))
      (node (ref "RV3") (pin "P$2") (pinfunction "S_P$2") (pintype "passive"))
    )
    (net (code "94") (name "POT4") (class "Default")
      (node (ref "J3") (pin "1") (pinfunction "PA3/AN3_1") (pintype "bidirectional"))
      (node (ref "RV4") (pin "P$2") (pinfunction "S_P$2") (pintype "passive"))
    )
    (net (code "95") (name "RESET") (class "Default")
      (node (ref "J3") (pin "90") (pinfunction "RESET_90") (pintype "bidirectional"))
      (node (ref "JTAG1") (pin "15") (pinfunction "15_15") (pintype "passive"))
    )
    (net (code "96") (name "RTS") (class "Default")
      (node (ref "J3") (pin "101") (pinfunction "PD4_101") (pintype "bidirectional"))
      (node (ref "XB1") (pin "16") (pinfunction "~{RTS}/AD6/DIO6_16") (pintype "bidirectional"))
    )
    (net (code "97") (name "RX") (class "Default")
      (node (ref "J3") (pin "115") (pinfunction "PB7_115") (pintype "bidirectional"))
      (node (ref "U1") (pin "D1") (pinfunction "D1_D1") (pintype "bidirectional"))
    )
    (net (code "98") (name "SCK") (class "Default")
      (node (ref "IC1") (pin "11") (pinfunction "SCK_11") (pintype "input"))
      (node (ref "IC2") (pin "11") (pinfunction "SCK_11") (pintype "input"))
      (node (ref "J3") (pin "43") (pinfunction "PB13_43") (pintype "bidirectional"))
      (node (ref "J5") (pin "3") (pinfunction "3_3") (pintype "passive"))
      (node (ref "U1") (pin "D13") (pinfunction "D13_D13") (pintype "bidirectional"))
      (node (ref "X1") (pin "13") (pinfunction "S_13") (pintype "passive"))
    )
    (net (code "99") (name "SCL") (class "Default")
      (node (ref "J3") (pin "37") (pinfunction "PB10_37") (pintype "bidirectional"))
      (node (ref "R11") (pin "1") (pinfunction "1_1") (pintype "passive"))
      (node (ref "U$30") (pin "26") (pinfunction "SCL_26") (pintype "bidirectional"))
      (node (ref "X1") (pin "10") (pinfunction "S_10") (pintype "passive"))
    )
    (net (code "100") (name "SCL1") (class "Default")
      (node (ref "J3") (pin "117") (pinfunction "PB8_117") (pintype "bidirectional"))
      (node (ref "U1") (pin "SCL") (pinfunction "SCL_SCL") (pintype "bidirectional"))
    )
    (net (code "101") (name "SDA") (class "Default")
      (node (ref "J3") (pin "39") (pinfunction "PB11_39") (pintype "bidirectional"))
      (node (ref "R10") (pin "1") (pinfunction "1_1") (pintype "passive"))
      (node (ref "U$30") (pin "27") (pinfunction "SDA_27") (pintype "bidirectional"))
      (node (ref "X1") (pin "9") (pinfunction "S_9") (pintype "passive"))
    )
    (net (code "102") (name "SDA1") (class "Default")
      (node (ref "J3") (pin "119") (pinfunction "PB9_119") (pintype "bidirectional"))
      (node (ref "U1") (pin "SDA") (pinfunction "SDA_SDA") (pintype "bidirectional"))
    )
    (net (code "103") (name "SDIO_CMD") (class "Default")
      (node (ref "J3") (pin "97") (pinfunction "PD2_97") (pintype "bidirectional"))
      (node (ref "R4") (pin "2") (pinfunction "2_2") (pintype "passive"))
      (node (ref "U$2") (pin "3") (pinfunction "DATA_IN_3") (pintype "input"))
    )
    (net (code "104") (name "SDIO_D0") (class "Default")
      (node (ref "J3") (pin "69") (pinfunction "PC8_69") (pintype "bidirectional"))
      (node (ref "R22") (pin "2") (pinfunction "2_2") (pintype "passive"))
      (node (ref "U$2") (pin "7") (pinfunction "DATA_OUT_7") (pintype "output"))
    )
    (net (code "105") (name "SDIO_D1") (class "Default")
      (node (ref "J3") (pin "71") (pinfunction "PC9_71") (pintype "bidirectional"))
      (node (ref "R6") (pin "2") (pinfunction "2_2") (pintype "passive"))
      (node (ref "U$2") (pin "8") (pinfunction "DAT1_8") (pintype "bidirectional"))
    )
    (net (code "106") (name "SDIO_D2") (class "Default")
      (node (ref "J3") (pin "87") (pinfunction "PC10_87") (pintype "bidirectional"))
      (node (ref "R8") (pin "2") (pinfunction "2_2") (pintype "passive"))
      (node (ref "U$2") (pin "1") (pinfunction "DAT2_1") (pintype "bidirectional"))
    )
    (net (code "107") (name "SDIO_D3") (class "Default")
      (node (ref "J3") (pin "89") (pinfunction "PC11_89") (pintype "bidirectional"))
      (node (ref "R5") (pin "2") (pinfunction "2_2") (pintype "passive"))
      (node (ref "U$2") (pin "2") (pinfunction "CS_2") (pintype "input"))
    )
    (net (code "108") (name "SDIO_SCK") (class "Default")
      (node (ref "J3") (pin "91") (pinfunction "PC12_91") (pintype "bidirectional"))
      (node (ref "U$2") (pin "5") (pinfunction "SCLK_5") (pintype "input"))
    )
    (net (code "109") (name "SD_IN") (class "Default")
      (node (ref "J3") (pin "73") (pinfunction "PA8_73") (pintype "bidirectional"))
      (node (ref "U$2") (pin "CD1") (pinfunction "CARD_DETECT_CD1") (pintype "passive"))
    )
    (net (code "110") (name "SW1") (class "Default")
      (node (ref "J3") (pin "25") (pinfunction "PE10_25") (pintype "bidirectional"))
      (node (ref "S5") (pin "P") (pinfunction "P_P") (pintype "passive"))
    )
    (net (code "111") (name "SW2") (class "Default")
      (node (ref "J3") (pin "23") (pinfunction "PE9_23") (pintype "bidirectional"))
      (node (ref "S6") (pin "P") (pinfunction "P_P") (pintype "passive"))
    )
    (net (code "112") (name "SW3") (class "Default")
      (node (ref "J3") (pin "21") (pinfunction "PE8_21") (pintype "bidirectional"))
      (node (ref "S7") (pin "P") (pinfunction "P_P") (pintype "passive"))
    )
    (net (code "113") (name "SW4") (class "Default")
      (node (ref "J3") (pin "19") (pinfunction "PE7_19") (pintype "bidirectional"))
      (node (ref "S8") (pin "P") (pinfunction "P_P") (pintype "passive"))
    )
    (net (code "114") (name "SW5") (class "Default")
      (node (ref "J3") (pin "17") (pinfunction "PB1/AN9_17") (pintype "bidirectional"))
      (node (ref "R12") (pin "1") (pinfunction "1_1") (pintype "passive"))
      (node (ref "S1") (pin "1") (pinfunction "S_1") (pintype "passive"))
      (node (ref "S1") (pin "2") (pinfunction "S1_2") (pintype "passive"))
    )
    (net (code "115") (name "SW6") (class "Default")
      (node (ref "J3") (pin "15") (pinfunction "PB0/AN8_15") (pintype "bidirectional"))
      (node (ref "R13") (pin "1") (pinfunction "1_1") (pintype "passive"))
      (node (ref "S2") (pin "1") (pinfunction "S_1") (pintype "passive"))
      (node (ref "S2") (pin "2") (pinfunction "S1_2") (pintype "passive"))
    )
    (net (code "116") (name "SW7") (class "Default")
      (node (ref "J3") (pin "13") (pinfunction "PC5/AN15_13") (pintype "bidirectional"))
      (node (ref "R14") (pin "1") (pinfunction "1_1") (pintype "passive"))
      (node (ref "S3") (pin "1") (pinfunction "S_1") (pintype "passive"))
      (node (ref "S3") (pin "2") (pinfunction "S1_2") (pintype "passive"))
    )
    (net (code "117") (name "SW8") (class "Default")
      (node (ref "J3") (pin "11") (pinfunction "PC4/AN15_11") (pintype "bidirectional"))
      (node (ref "R15") (pin "1") (pinfunction "1_1") (pintype "passive"))
      (node (ref "S4") (pin "1") (pinfunction "S_1") (pintype "passive"))
      (node (ref "S4") (pin "2") (pinfunction "S1_2") (pintype "passive"))
    )
    (net (code "118") (name "TELE_RX") (class "Default")
      (node (ref "J3") (pin "105") (pinfunction "PD6_105") (pintype "bidirectional"))
      (node (ref "R25") (pin "2") (pinfunction "2_2") (pintype "passive"))
      (node (ref "R27") (pin "1") (pinfunction "1_1") (pintype "passive"))
      (node (ref "XB1") (pin "2") (pinfunction "DOUT_2") (pintype "output"))
    )
    (net (code "119") (name "TELE_TX") (class "Default")
      (node (ref "J3") (pin "103") (pinfunction "PD5_103") (pintype "bidirectional"))
      (node (ref "U4") (pin "40") (pinfunction "P0/RX_40") (pintype "bidirectional"))
      (node (ref "XB1") (pin "3") (pinfunction "DIN/~{CONFIG}_3") (pintype "input"))
    )
    (net (code "120") (name "TX") (class "Default")
      (node (ref "J3") (pin "113") (pinfunction "PB6_113") (pintype "bidirectional"))
      (node (ref "U1") (pin "D0") (pinfunction "D0_D0") (pintype "bidirectional"))
    )
    (net (code "121") (name "VBUS") (class "Default")
      (node (ref "CN1") (pin "VBUS") (pinfunction "VBUS_VBUS") (pintype "power_in"))
    )
    (net (code "122") (name "unconnected-(DIS1-NC-Pad15)") (class "Default")
      (node (ref "DIS1") (pin "15") (pinfunction "NC_15") (pintype "no_connect"))
    )
    (net (code "123") (name "unconnected-(DIS1-NC-Pad16)") (class "Default")
      (node (ref "DIS1") (pin "16") (pinfunction "NC_16") (pintype "no_connect"))
    )
    (net (code "124") (name "unconnected-(IC2A-QD-Pad3)") (class "Default")
      (node (ref "IC2") (pin "3") (pinfunction "QD_3") (pintype "tri_state"))
    )
    (net (code "125") (name "unconnected-(IC2A-QE-Pad4)") (class "Default")
      (node (ref "IC2") (pin "4") (pinfunction "QE_4") (pintype "tri_state"))
    )
    (net (code "126") (name "unconnected-(IC2A-QF-Pad5)") (class "Default")
      (node (ref "IC2") (pin "5") (pinfunction "QF_5") (pintype "tri_state"))
    )
    (net (code "127") (name "unconnected-(IC2A-QG-Pad6)") (class "Default")
      (node (ref "IC2") (pin "6") (pinfunction "QG_6") (pintype "tri_state"))
    )
    (net (code "128") (name "unconnected-(IC2A-QH*-Pad9)") (class "Default")
      (node (ref "IC2") (pin "9") (pinfunction "QH*_9") (pintype "tri_state"))
    )
    (net (code "129") (name "unconnected-(IC2A-QH-Pad7)") (class "Default")
      (node (ref "IC2") (pin "7") (pinfunction "QH_7") (pintype "tri_state"))
    )
    (net (code "130") (name "unconnected-(J1-Pad1)") (class "Default")
      (node (ref "J1") (pin "1") (pinfunction "1_1") (pintype "passive"))
    )
    (net (code "131") (name "unconnected-(J1-Pad4)") (class "Default")
      (node (ref "J1") (pin "4") (pinfunction "4_4") (pintype "passive"))
    )
    (net (code "132") (name "unconnected-(J1-Pad5)") (class "Default")
      (node (ref "J1") (pin "5") (pinfunction "5_5") (pintype "passive"))
    )
    (net (code "133") (name "unconnected-(J1-Pad8)") (class "Default")
      (node (ref "J1") (pin "8") (pinfunction "8_8") (pintype "passive"))
    )
    (net (code "134") (name "unconnected-(J1-Pad9)") (class "Default")
      (node (ref "J1") (pin "9") (pinfunction "9_9") (pintype "passive"))
    )
    (net (code "135") (name "unconnected-(J3B-PE11-Pad27)") (class "Default")
      (node (ref "J3") (pin "27") (pinfunction "PE11_27") (pintype "bidirectional"))
    )
    (net (code "136") (name "unconnected-(J3B-PE12-Pad29)") (class "Default")
      (node (ref "J3") (pin "29") (pinfunction "PE12_29") (pintype "bidirectional"))
    )
    (net (code "137") (name "unconnected-(J3B-PE13-Pad31)") (class "Default")
      (node (ref "J3") (pin "31") (pinfunction "PE13_31") (pintype "bidirectional"))
    )
    (net (code "138") (name "unconnected-(J3B-PE14-Pad33)") (class "Default")
      (node (ref "J3") (pin "33") (pinfunction "PE14_33") (pintype "bidirectional"))
    )
    (net (code "139") (name "unconnected-(J3D-PD7-Pad107)") (class "Default")
      (node (ref "J3") (pin "107") (pinfunction "PD7_107") (pintype "bidirectional"))
    )
    (net (code "140") (name "unconnected-(J3D-PE0-Pad121)") (class "Default")
      (node (ref "J3") (pin "121") (pinfunction "PE0_121") (pintype "bidirectional"))
    )
    (net (code "141") (name "unconnected-(J3D-PE1-Pad123)") (class "Default")
      (node (ref "J3") (pin "123") (pinfunction "PE1_123") (pintype "bidirectional"))
    )
    (net (code "142") (name "unconnected-(J3E-PE2-Pad133)") (class "Default")
      (node (ref "J3") (pin "133") (pinfunction "PE2_133") (pintype "bidirectional"))
    )
    (net (code "143") (name "unconnected-(J4-CTS-PadP$5)") (class "Default")
      (node (ref "J4") (pin "P$5") (pinfunction "CTS_P$5") (pintype "bidirectional"))
    )
    (net (code "144") (name "unconnected-(J4-DTR-PadP$1)") (class "Default")
      (node (ref "J4") (pin "P$1") (pinfunction "DTR_P$1") (pintype "bidirectional"))
    )
    (net (code "145") (name "unconnected-(J4-VCC-PadP$4)") (class "Default")
      (node (ref "J4") (pin "P$4") (pinfunction "VCC_P$4") (pintype "bidirectional"))
    )
    (net (code "146") (name "unconnected-(J5-Pad5)") (class "Default")
      (node (ref "J5") (pin "5") (pinfunction "5_5") (pintype "passive"))
    )
    (net (code "147") (name "unconnected-(JTAG1-Pad11)") (class "Default")
      (node (ref "JTAG1") (pin "11") (pinfunction "11_11") (pintype "passive"))
    )
    (net (code "148") (name "unconnected-(JTAG1-Pad17)") (class "Default")
      (node (ref "JTAG1") (pin "17") (pinfunction "17_17") (pintype "passive"))
    )
    (net (code "149") (name "unconnected-(JTAG1-Pad19)") (class "Default")
      (node (ref "JTAG1") (pin "19") (pinfunction "19_19") (pintype "passive"))
    )
    (net (code "150") (name "unconnected-(SW1-O1-PadP$1)") (class "Default")
      (node (ref "SW1") (pin "P$1") (pinfunction "O1_P$1") (pintype "passive"))
    )
    (net (code "151") (name "unconnected-(SW1-O2-PadP$6)") (class "Default")
      (node (ref "SW1") (pin "P$6") (pinfunction "O2_P$6") (pintype "passive"))
    )
    (net (code "152") (name "unconnected-(U$2-CARD_DETECT1-PadCD2)") (class "Default")
      (node (ref "U$2") (pin "CD2") (pinfunction "CARD_DETECT1_CD2") (pintype "passive"))
    )
    (net (code "153") (name "unconnected-(U$30-{slash}OUT15-Pad23)") (class "Default")
      (node (ref "U$30") (pin "23") (pinfunction "/OUT15_23") (pintype "bidirectional"))
    )
    (net (code "154") (name "unconnected-(U1-PadAREF)") (class "Default")
      (node (ref "U1") (pin "AREF") (pinfunction "AREF_AREF") (pintype "bidirectional"))
    )
    (net (code "155") (name "unconnected-(U1-PadRESERVED)") (class "Default")
      (node (ref "U1") (pin "RESERVED") (pinfunction "RESERVED_RESERVED") (pintype "no_connect"))
    )
    (net (code "156") (name "unconnected-(U1-{slash}RESET-PadRESET)") (class "Default")
      (node (ref "U1") (pin "RESET") (pinfunction "/RESET_RESET") (pintype "bidirectional"))
    )
    (net (code "157") (name "unconnected-(U4-CLK-Pad34)") (class "Default")
      (node (ref "U4") (pin "34") (pinfunction "CLK_34") (pintype "bidirectional"))
    )
    (net (code "158") (name "unconnected-(U4-MISO-Pad38)") (class "Default")
      (node (ref "U4") (pin "38") (pinfunction "MISO_38") (pintype "bidirectional"))
    )
    (net (code "159") (name "unconnected-(U4-MOSI-Pad16)") (class "Default")
      (node (ref "U4") (pin "16") (pinfunction "MOSI_16") (pintype "bidirectional"))
    )
    (net (code "160") (name "unconnected-(U4-P2-Pad23)") (class "Default")
      (node (ref "U4") (pin "23") (pinfunction "P2_23") (pintype "bidirectional"))
    )
    (net (code "161") (name "unconnected-(U4-P3-Pad24)") (class "Default")
      (node (ref "U4") (pin "24") (pinfunction "P3_24") (pintype "bidirectional"))
    )
    (net (code "162") (name "unconnected-(U4-P4-Pad21)") (class "Default")
      (node (ref "U4") (pin "21") (pinfunction "P4_21") (pintype "bidirectional"))
    )
    (net (code "163") (name "unconnected-(U4-P8-Pad22)") (class "Default")
      (node (ref "U4") (pin "22") (pinfunction "P8_22") (pintype "bidirectional"))
    )
    (net (code "164") (name "unconnected-(U4-P9-Pad18)") (class "Default")
      (node (ref "U4") (pin "18") (pinfunction "P9_18") (pintype "bidirectional"))
    )
    (net (code "165") (name "unconnected-(U4-P10-Pad20)") (class "Default")
      (node (ref "U4") (pin "20") (pinfunction "P10_20") (pintype "bidirectional"))
    )
    (net (code "166") (name "unconnected-(U4-P11-Pad39)") (class "Default")
      (node (ref "U4") (pin "39") (pinfunction "P11_39") (pintype "bidirectional"))
    )
    (net (code "167") (name "unconnected-(U4-P12-Pad42)") (class "Default")
      (node (ref "U4") (pin "42") (pinfunction "P12_42") (pintype "bidirectional"))
    )
    (net (code "168") (name "unconnected-(U4-P13-Pad5)") (class "Default")
      (node (ref "U4") (pin "5") (pinfunction "P13_5") (pintype "bidirectional"))
    )
    (net (code "169") (name "unconnected-(U4-P14-Pad6)") (class "Default")
      (node (ref "U4") (pin "6") (pinfunction "P14_6") (pintype "bidirectional"))
    )
    (net (code "170") (name "unconnected-(U4-P15-Pad7)") (class "Default")
      (node (ref "U4") (pin "7") (pinfunction "P15_7") (pintype "bidirectional"))
    )
    (net (code "171") (name "unconnected-(U4-P16-Pad8)") (class "Default")
      (node (ref "U4") (pin "8") (pinfunction "P16_8") (pintype "bidirectional"))
    )
    (net (code "172") (name "unconnected-(U4-P17-Pad11)") (class "Default")
      (node (ref "U4") (pin "11") (pinfunction "P17_11") (pintype "bidirectional"))
    )
    (net (code "173") (name "unconnected-(U4-P18-Pad10)") (class "Default")
      (node (ref "U4") (pin "10") (pinfunction "P18_10") (pintype "bidirectional"))
    )
    (net (code "174") (name "unconnected-(U4-P19-Pad12)") (class "Default")
      (node (ref "U4") (pin "12") (pinfunction "P19_12") (pintype "bidirectional"))
    )
    (net (code "175") (name "unconnected-(U4-P20-Pad13)") (class "Default")
      (node (ref "U4") (pin "13") (pinfunction "P20_13") (pintype "bidirectional"))
    )
    (net (code "176") (name "unconnected-(U4-P21-Pad15)") (class "Default")
      (node (ref "U4") (pin "15") (pinfunction "P21_15") (pintype "bidirectional"))
    )
    (net (code "177") (name "unconnected-(U4-P22-Pad14)") (class "Default")
      (node (ref "U4") (pin "14") (pinfunction "P22_14") (pintype "bidirectional"))
    )
    (net (code "178") (name "unconnected-(U4-P23-Pad17)") (class "Default")
      (node (ref "U4") (pin "17") (pinfunction "P23_17") (pintype "bidirectional"))
    )
    (net (code "179") (name "unconnected-(U4-Pad3,3V)") (class "Default")
      (node (ref "U4") (pin "3,3V") (pinfunction "3,3V_3,3V") (pintype "bidirectional"))
    )
    (net (code "180") (name "unconnected-(U4-RST-Pad9)") (class "Default")
      (node (ref "U4") (pin "9") (pinfunction "RST_9") (pintype "bidirectional"))
    )
    (net (code "181") (name "unconnected-(U10-NC-Pad8)") (class "Default")
      (node (ref "U10") (pin "8") (pinfunction "NC_8") (pintype "no_connect"))
    )
    (net (code "182") (name "unconnected-(U10-NC_2-Pad5)") (class "Default")
      (node (ref "U10") (pin "5") (pinfunction "NC_2_5") (pintype "no_connect"))
    )
    (net (code "183") (name "unconnected-(XB1-AD0{slash}DIO0-Pad20)") (class "Default")
      (node (ref "XB1") (pin "20") (pinfunction "AD0/DIO0_20") (pintype "bidirectional"))
    )
    (net (code "184") (name "unconnected-(XB1-AD1{slash}DIO1-Pad19)") (class "Default")
      (node (ref "XB1") (pin "19") (pinfunction "AD1/DIO1_19") (pintype "bidirectional"))
    )
    (net (code "185") (name "unconnected-(XB1-AD2{slash}DIO2-Pad18)") (class "Default")
      (node (ref "XB1") (pin "18") (pinfunction "AD2/DIO2_18") (pintype "bidirectional"))
    )
    (net (code "186") (name "unconnected-(XB1-CD{slash}DOUT_EN{slash}DO8-Pad4)") (class "Default")
      (node (ref "XB1") (pin "4") (pinfunction "CD/DOUT_EN/DO8_4") (pintype "output"))
    )
    (net (code "187") (name "unconnected-(XB1-COORD_SEL{slash}AD3{slash}DIO3-Pad17)") (class "Default")
      (node (ref "XB1") (pin "17") (pinfunction "COORD_SEL/AD3/DIO3_17") (pintype "bidirectional"))
    )
    (net (code "188") (name "unconnected-(XB1-ON{slash}~{SLEEP}-Pad13)") (class "Default")
      (node (ref "XB1") (pin "13") (pinfunction "ON/~{SLEEP}_13") (pintype "output"))
    )
    (net (code "189") (name "unconnected-(XB1-RF_TX{slash}AD4{slash}DIO4-Pad11)") (class "Default")
      (node (ref "XB1") (pin "11") (pinfunction "RF_TX/AD4/DIO4_11") (pintype "bidirectional"))
    )
    (net (code "190") (name "unconnected-(XB1-VREF-Pad14)") (class "Default")
      (node (ref "XB1") (pin "14") (pinfunction "VREF_14") (pintype "input"))
    )
    (net (code "191") (name "unconnected-(XB1-~{DTR}{slash}SLEEP_RQ{slash}DI8-Pad9)") (class "Default")
      (node (ref "XB1") (pin "9") (pinfunction "~{DTR}/SLEEP_RQ/DI8_9") (pintype "bidirectional"))
    )
    (net (code "192") (name "~{RESET}") (class "Default")
      (node (ref "J3") (pin "35") (pinfunction "PE15_35") (pintype "bidirectional"))
      (node (ref "U$30") (pin "25") (pinfunction "/RESET_25") (pintype "bidirectional"))
    )
  )
)
